# Tiny_UniProg.net
KiCad netlist of a schematic drawn in EAGLE
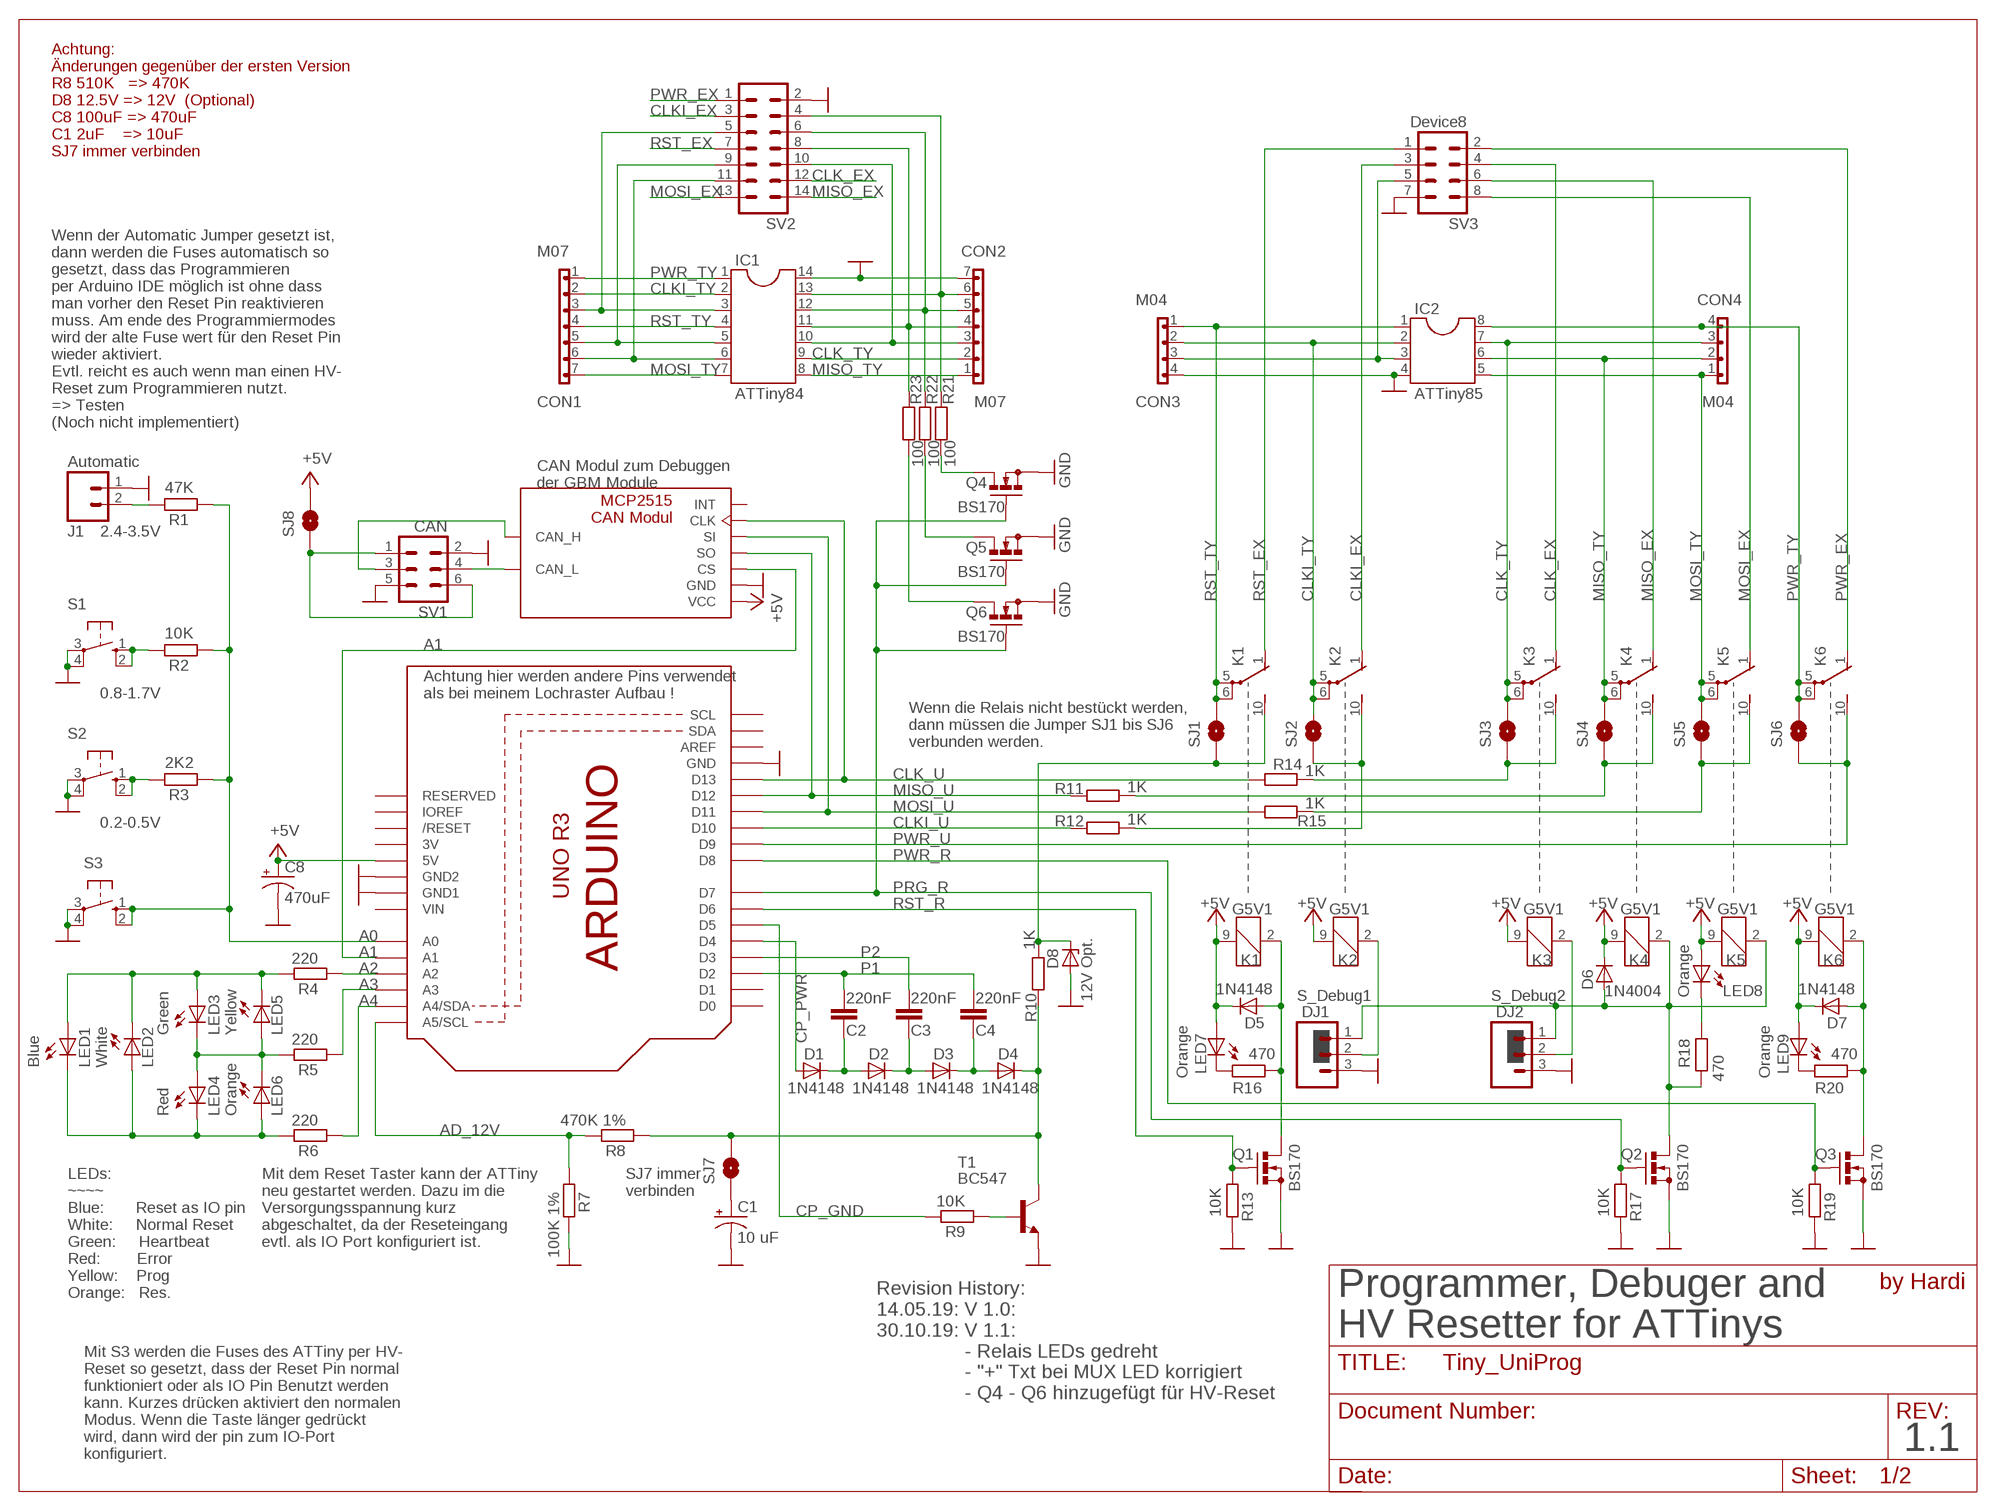
[diagram p0: schematic, sheet 1]
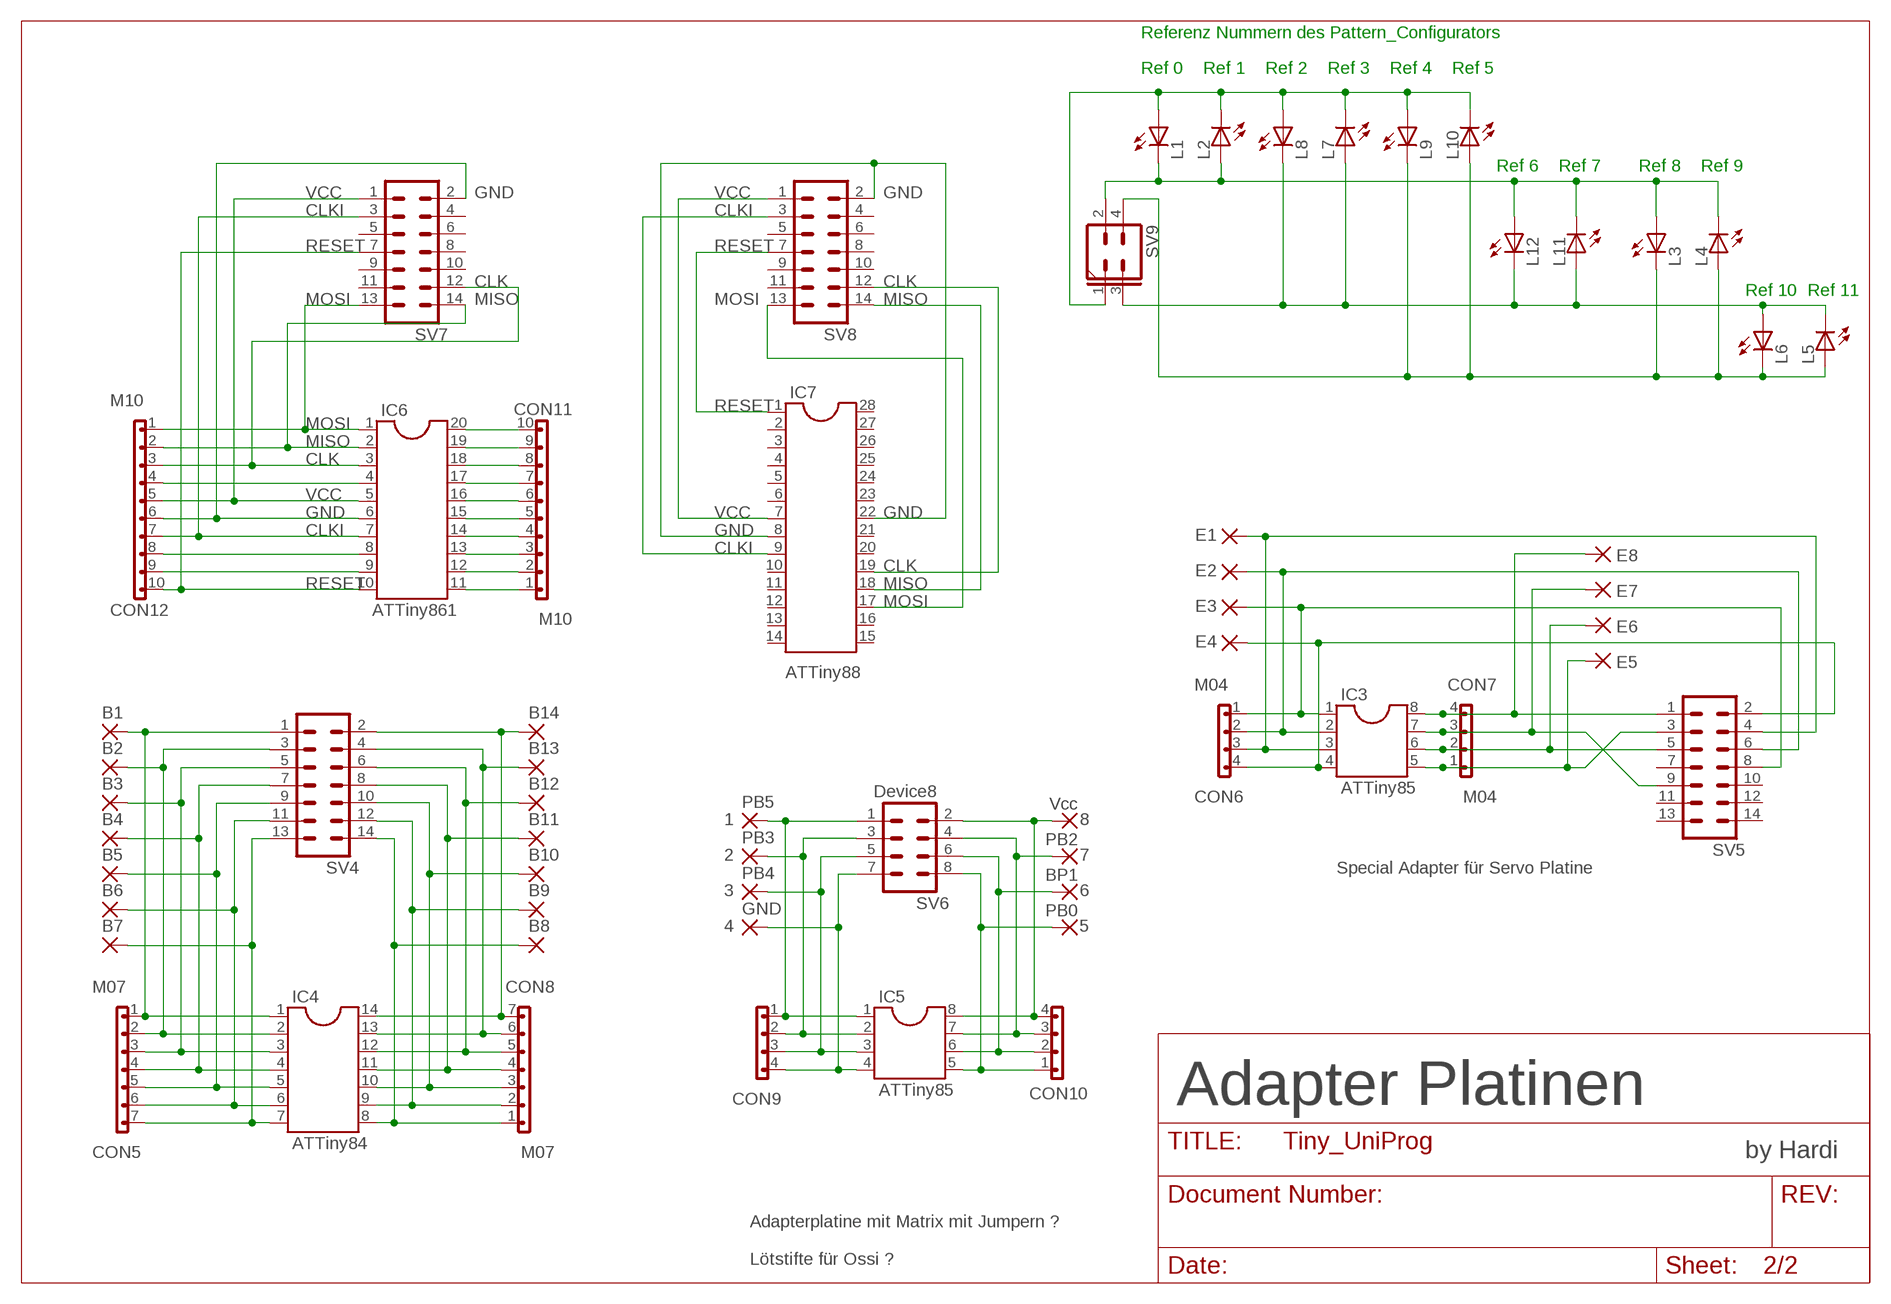
[diagram p1: schematic, sheet 2]

(export (version "E")
  (design (tool "Eeschema 10.0.6"))
  (components
    (comp (ref "1")
      (value "PB5")
      (footprint "eagle-import:2,54_1,0")
      (libsource (lib "eagle-import") (part "2,54/1,0"))
    )
    (comp (ref "2")
      (value "PB3")
      (footprint "eagle-import:2,54_1,0")
      (libsource (lib "eagle-import") (part "2,54/1,0"))
    )
    (comp (ref "3")
      (value "PB4")
      (footprint "eagle-import:2,54_1,0")
      (libsource (lib "eagle-import") (part "2,54/1,0"))
    )
    (comp (ref "4")
      (value "GND")
      (footprint "eagle-import:2,54_1,0")
      (libsource (lib "eagle-import") (part "2,54/1,0"))
    )
    (comp (ref "5")
      (value "PB0")
      (footprint "eagle-import:2,54_1,0")
      (libsource (lib "eagle-import") (part "2,54/1,0"))
    )
    (comp (ref "6")
      (value "BP1")
      (footprint "eagle-import:2,54_1,0")
      (libsource (lib "eagle-import") (part "2,54/1,0"))
    )
    (comp (ref "7")
      (value "PB2")
      (footprint "eagle-import:2,54_1,0")
      (libsource (lib "eagle-import") (part "2,54/1,0"))
    )
    (comp (ref "8")
      (value "Vcc")
      (footprint "eagle-import:2,54_1,0")
      (libsource (lib "eagle-import") (part "2,54/1,0"))
    )
    (comp (ref "B1")
      (value "2,54/1,0")
      (footprint "eagle-import:2,54_1,0")
      (libsource (lib "eagle-import") (part "2,54/1,0"))
    )
    (comp (ref "B2")
      (value "2,54/1,0")
      (footprint "eagle-import:2,54_1,0")
      (libsource (lib "eagle-import") (part "2,54/1,0"))
    )
    (comp (ref "B3")
      (value "2,54/1,0")
      (footprint "eagle-import:2,54_1,0")
      (libsource (lib "eagle-import") (part "2,54/1,0"))
    )
    (comp (ref "B4")
      (value "2,54/1,0")
      (footprint "eagle-import:2,54_1,0")
      (libsource (lib "eagle-import") (part "2,54/1,0"))
    )
    (comp (ref "B5")
      (value "2,54/1,0")
      (footprint "eagle-import:2,54_1,0")
      (libsource (lib "eagle-import") (part "2,54/1,0"))
    )
    (comp (ref "B6")
      (value "2,54/1,0")
      (footprint "eagle-import:2,54_1,0")
      (libsource (lib "eagle-import") (part "2,54/1,0"))
    )
    (comp (ref "B7")
      (value "2,54/1,0")
      (footprint "eagle-import:2,54_1,0")
      (libsource (lib "eagle-import") (part "2,54/1,0"))
    )
    (comp (ref "B8")
      (value "2,54/1,0")
      (footprint "eagle-import:2,54_1,0")
      (libsource (lib "eagle-import") (part "2,54/1,0"))
    )
    (comp (ref "B9")
      (value "2,54/1,0")
      (footprint "eagle-import:2,54_1,0")
      (libsource (lib "eagle-import") (part "2,54/1,0"))
    )
    (comp (ref "B10")
      (value "2,54/1,0")
      (footprint "eagle-import:2,54_1,0")
      (libsource (lib "eagle-import") (part "2,54/1,0"))
    )
    (comp (ref "B11")
      (value "2,54/1,0")
      (footprint "eagle-import:2,54_1,0")
      (libsource (lib "eagle-import") (part "2,54/1,0"))
    )
    (comp (ref "B12")
      (value "2,54/1,0")
      (footprint "eagle-import:2,54_1,0")
      (libsource (lib "eagle-import") (part "2,54/1,0"))
    )
    (comp (ref "B13")
      (value "2,54/1,0")
      (footprint "eagle-import:2,54_1,0")
      (libsource (lib "eagle-import") (part "2,54/1,0"))
    )
    (comp (ref "B14")
      (value "2,54/1,0")
      (footprint "eagle-import:2,54_1,0")
      (libsource (lib "eagle-import") (part "2,54/1,0"))
    )
    (comp (ref "CON5")
      (value "M07")
      (footprint "eagle-import:1X07")
      (libsource (lib "eagle-import") (part "M07"))
    )
    (comp (ref "CON6")
      (value "M04")
      (footprint "eagle-import:1X04")
      (libsource (lib "eagle-import") (part "M04"))
    )
    (comp (ref "CON7")
      (value "M04")
      (footprint "eagle-import:1X04")
      (libsource (lib "eagle-import") (part "M04"))
    )
    (comp (ref "CON8")
      (value "M07")
      (footprint "eagle-import:1X07")
      (libsource (lib "eagle-import") (part "M07"))
    )
    (comp (ref "CON9")
      (value "M04")
      (footprint "eagle-import:1X04")
      (libsource (lib "eagle-import") (part "M04"))
    )
    (comp (ref "CON10")
      (value "M04")
      (footprint "eagle-import:1X04")
      (libsource (lib "eagle-import") (part "M04"))
    )
    (comp (ref "CON11")
      (value "M10")
      (footprint "eagle-import:1X10")
      (libsource (lib "eagle-import") (part "M10"))
    )
    (comp (ref "CON12")
      (value "M10")
      (footprint "eagle-import:1X10")
      (libsource (lib "eagle-import") (part "M10"))
    )
    (comp (ref "E1")
      (value "2,54/1,0")
      (footprint "eagle-import:2,54_1,0")
      (libsource (lib "eagle-import") (part "2,54/1,0"))
    )
    (comp (ref "E2")
      (value "2,54/1,0")
      (footprint "eagle-import:2,54_1,0")
      (libsource (lib "eagle-import") (part "2,54/1,0"))
    )
    (comp (ref "E3")
      (value "2,54/1,0")
      (footprint "eagle-import:2,54_1,0")
      (libsource (lib "eagle-import") (part "2,54/1,0"))
    )
    (comp (ref "E4")
      (value "2,54/1,0")
      (footprint "eagle-import:2,54_1,0")
      (libsource (lib "eagle-import") (part "2,54/1,0"))
    )
    (comp (ref "E5")
      (value "2,54/1,0")
      (footprint "eagle-import:2,54_1,0")
      (libsource (lib "eagle-import") (part "2,54/1,0"))
    )
    (comp (ref "E6")
      (value "2,54/1,0")
      (footprint "eagle-import:2,54_1,0")
      (libsource (lib "eagle-import") (part "2,54/1,0"))
    )
    (comp (ref "E7")
      (value "2,54/1,0")
      (footprint "eagle-import:2,54_1,0")
      (libsource (lib "eagle-import") (part "2,54/1,0"))
    )
    (comp (ref "E8")
      (value "2,54/1,0")
      (footprint "eagle-import:2,54_1,0")
      (libsource (lib "eagle-import") (part "2,54/1,0"))
    )
    (comp (ref "IC3")
      (value "ATTiny85")
      (footprint "eagle-import:DIL08")
      (libsource (lib "eagle-import") (part "DIL8"))
    )
    (comp (ref "IC4")
      (value "ATTiny84")
      (footprint "eagle-import:DIL14")
      (libsource (lib "eagle-import") (part "DIL14"))
    )
    (comp (ref "IC5")
      (value "ATTiny85")
      (footprint "eagle-import:DIL08")
      (libsource (lib "eagle-import") (part "DIL8"))
    )
    (comp (ref "IC6")
      (value "ATTiny861")
      (footprint "eagle-import:DIL20")
      (libsource (lib "eagle-import") (part "DIL20"))
    )
    (comp (ref "IC7")
      (value "DIL28-3")
      (footprint "eagle-import:DIL28-3")
      (libsource (lib "eagle-import") (part "DIL28-3"))
    )
    (comp (ref "L1")
      (value "LED3MM")
      (footprint "eagle-import:LED3MM")
      (libsource (lib "eagle-import") (part "LED3MM"))
    )
    (comp (ref "L2")
      (value "LED3MM")
      (footprint "eagle-import:LED3MM")
      (libsource (lib "eagle-import") (part "LED3MM"))
    )
    (comp (ref "L3")
      (value "LED3MM")
      (footprint "eagle-import:LED3MM")
      (libsource (lib "eagle-import") (part "LED3MM"))
    )
    (comp (ref "L4")
      (value "LED3MM")
      (footprint "eagle-import:LED3MM")
      (libsource (lib "eagle-import") (part "LED3MM"))
    )
    (comp (ref "L5")
      (value "LED3MM")
      (footprint "eagle-import:LED3MM")
      (libsource (lib "eagle-import") (part "LED3MM"))
    )
    (comp (ref "L6")
      (value "LED3MM")
      (footprint "eagle-import:LED3MM")
      (libsource (lib "eagle-import") (part "LED3MM"))
    )
    (comp (ref "L7")
      (value "LED3MM")
      (footprint "eagle-import:LED3MM")
      (libsource (lib "eagle-import") (part "LED3MM"))
    )
    (comp (ref "L8")
      (value "LED3MM")
      (footprint "eagle-import:LED3MM")
      (libsource (lib "eagle-import") (part "LED3MM"))
    )
    (comp (ref "L9")
      (value "LED3MM")
      (footprint "eagle-import:LED3MM")
      (libsource (lib "eagle-import") (part "LED3MM"))
    )
    (comp (ref "L10")
      (value "LED3MM")
      (footprint "eagle-import:LED3MM")
      (libsource (lib "eagle-import") (part "LED3MM"))
    )
    (comp (ref "L11")
      (value "LED3MM")
      (footprint "eagle-import:LED3MM")
      (libsource (lib "eagle-import") (part "LED3MM"))
    )
    (comp (ref "L12")
      (value "LED3MM")
      (footprint "eagle-import:LED3MM")
      (libsource (lib "eagle-import") (part "LED3MM"))
    )
    (comp (ref "SV4")
      (value "ML14")
      (footprint "eagle-import:ML14")
      (libsource (lib "eagle-import") (part "ML14"))
    )
    (comp (ref "SV5")
      (value "ML14")
      (footprint "eagle-import:ML14")
      (libsource (lib "eagle-import") (part "ML14"))
    )
    (comp (ref "SV6")
      (value "Device8")
      (footprint "eagle-import:CON-HARTING-ML_ML08")
      (libsource (lib "eagle-import") (part "CON-HARTING-ML_ML08"))
    )
    (comp (ref "SV7")
      (value "ML14")
      (footprint "eagle-import:ML14")
      (libsource (lib "eagle-import") (part "ML14"))
    )
    (comp (ref "SV8")
      (value "ML14")
      (footprint "eagle-import:ML14")
      (libsource (lib "eagle-import") (part "ML14"))
    )
    (comp (ref "SV9")
      (value "MA02-2MUX-SIGNAL")
      (footprint "eagle-import:MUX-SIGNAL")
      (libsource (lib "eagle-import") (part "MA02-2MUX-SIGNAL"))
    )
    (comp (ref "C1")
      (value "10 uF")
      (footprint "eagle-import:CPOL-RADIAL-10UF-63V")
      (libsource (lib "eagle-import") (part "100UF-25V-20%(PTH)D5MM"))
    )
    (comp (ref "C2")
      (value "220nF")
      (footprint "eagle-import:C050-024X044")
      (libsource (lib "eagle-import") (part "C-EU050-024X044"))
    )
    (comp (ref "C3")
      (value "220nF")
      (footprint "eagle-import:C050-024X044")
      (libsource (lib "eagle-import") (part "C-EU050-024X044"))
    )
    (comp (ref "C4")
      (value "220nF")
      (footprint "eagle-import:C050-024X044")
      (libsource (lib "eagle-import") (part "C-EU050-024X044"))
    )
    (comp (ref "C8")
      (value "470uF")
      (footprint "eagle-import:SPARKFUN-CAPACITORS_CPOL-RADIAL-100UF-25V")
      (libsource (lib "eagle-import") (part "SPARKFUN-CAPACITORS_100UF-25V-20%(PTH)"))
    )
    (comp (ref "CAN1")
      (value "MCP2515_CAN_MODUL")
      (footprint "eagle-import:MCP2515_CAN_MODUL")
      (libsource (lib "eagle-import") (part "MCP2515_CAN_MODUL"))
    )
    (comp (ref "CON1")
      (value "M07")
      (footprint "eagle-import:1X07")
      (libsource (lib "eagle-import") (part "M07"))
    )
    (comp (ref "CON2")
      (value "M07")
      (footprint "eagle-import:1X07")
      (libsource (lib "eagle-import") (part "M07"))
    )
    (comp (ref "CON3")
      (value "M04")
      (footprint "eagle-import:1X04")
      (libsource (lib "eagle-import") (part "M04"))
    )
    (comp (ref "CON4")
      (value "M04")
      (footprint "eagle-import:1X04")
      (libsource (lib "eagle-import") (part "M04"))
    )
    (comp (ref "D1")
      (value "1N4148")
      (footprint "eagle-import:DO35-2")
      (libsource (lib "eagle-import") (part "1N4148DO35-2"))
    )
    (comp (ref "D2")
      (value "1N4148")
      (footprint "eagle-import:DO35-2")
      (libsource (lib "eagle-import") (part "1N4148DO35-2"))
    )
    (comp (ref "D3")
      (value "1N4148")
      (footprint "eagle-import:DO35-2")
      (libsource (lib "eagle-import") (part "1N4148DO35-2"))
    )
    (comp (ref "D4")
      (value "1N4148")
      (footprint "eagle-import:DO35-2")
      (libsource (lib "eagle-import") (part "1N4148DO35-2"))
    )
    (comp (ref "D5")
      (value "1N4148")
      (footprint "eagle-import:DO35-2")
      (libsource (lib "eagle-import") (part "1N4148DO35-2"))
    )
    (comp (ref "D6")
      (value "1N4004")
      (footprint "eagle-import:DO35-2")
      (libsource (lib "eagle-import") (part "1N4004DO35-2"))
    )
    (comp (ref "D7")
      (value "1N4148")
      (footprint "eagle-import:DO35-2")
      (libsource (lib "eagle-import") (part "1N4148DO35-2"))
    )
    (comp (ref "D8")
      (value "12V Opt.")
      (footprint "eagle-import:ZDIO-2.5")
      (libsource (lib "eagle-import") (part "ZENER-DIODEZD-2.5"))
    )
    (comp (ref "DJ1")
      (value "S_Debug1")
      (footprint "eagle-import:1X03")
      (libsource (lib "eagle-import") (part "M03PTH"))
    )
    (comp (ref "DJ2")
      (value "S_Debug2")
      (footprint "eagle-import:1X03")
      (libsource (lib "eagle-import") (part "M03PTH"))
    )
    (comp (ref "IC1")
      (value "ATTiny84")
      (footprint "eagle-import:DIL14")
      (libsource (lib "eagle-import") (part "DIL14"))
    )
    (comp (ref "IC2")
      (value "ATTiny85")
      (footprint "eagle-import:DIL08")
      (libsource (lib "eagle-import") (part "DIL8"))
    )
    (comp (ref "J1")
      (value "Automatic")
      (footprint "eagle-import:1X02")
      (libsource (lib "eagle-import") (part "M02PTH"))
    )
    (comp (ref "K1")
      (value "G5V1")
      (footprint "eagle-import:G5V1")
      (fields (field (name "MPN") "G5V-1-DC24"))
      (libsource (lib "eagle-import") (part "G5V1"))
    )
    (comp (ref "K2")
      (value "G5V1")
      (footprint "eagle-import:G5V1")
      (fields (field (name "MPN") "G5V-1-DC24"))
      (libsource (lib "eagle-import") (part "G5V1"))
    )
    (comp (ref "K3")
      (value "G5V1")
      (footprint "eagle-import:G5V1")
      (fields (field (name "MPN") "G5V-1-DC24"))
      (libsource (lib "eagle-import") (part "G5V1"))
    )
    (comp (ref "K4")
      (value "G5V1")
      (footprint "eagle-import:G5V1")
      (fields (field (name "MPN") "G5V-1-DC24"))
      (libsource (lib "eagle-import") (part "G5V1"))
    )
    (comp (ref "K5")
      (value "G5V1")
      (footprint "eagle-import:G5V1")
      (fields (field (name "MPN") "G5V-1-DC24"))
      (libsource (lib "eagle-import") (part "G5V1"))
    )
    (comp (ref "K6")
      (value "G5V1")
      (footprint "eagle-import:G5V1")
      (fields (field (name "MPN") "G5V-1-DC24"))
      (libsource (lib "eagle-import") (part "G5V1"))
    )
    (comp (ref "LED1")
      (value "Blue")
      (footprint "eagle-import:LED3MM")
      (libsource (lib "eagle-import") (part "LED3MM"))
    )
    (comp (ref "LED2")
      (value "White")
      (footprint "eagle-import:LED3MM")
      (libsource (lib "eagle-import") (part "LED3MM"))
    )
    (comp (ref "LED3")
      (value "Green")
      (footprint "eagle-import:LED3MM")
      (libsource (lib "eagle-import") (part "LED3MM"))
    )
    (comp (ref "LED4")
      (value "Red")
      (footprint "eagle-import:LED3MM")
      (libsource (lib "eagle-import") (part "LED3MM"))
    )
    (comp (ref "LED5")
      (value "Yellow")
      (footprint "eagle-import:LED3MM")
      (libsource (lib "eagle-import") (part "LED3MM"))
    )
    (comp (ref "LED6")
      (value "Orange")
      (footprint "eagle-import:LED3MM")
      (libsource (lib "eagle-import") (part "LED3MM"))
    )
    (comp (ref "LED7")
      (value "Orange")
      (footprint "eagle-import:LED3MM")
      (libsource (lib "eagle-import") (part "LED3MM"))
    )
    (comp (ref "LED8")
      (value "Orange")
      (footprint "eagle-import:LED3MM")
      (libsource (lib "eagle-import") (part "LED3MM"))
    )
    (comp (ref "LED9")
      (value "Orange")
      (footprint "eagle-import:LED3MM")
      (libsource (lib "eagle-import") (part "LED3MM"))
    )
    (comp (ref "Q1")
      (value "BS170")
      (footprint "eagle-import:SOT54E")
      (libsource (lib "eagle-import") (part "BS170"))
    )
    (comp (ref "Q2")
      (value "BS170")
      (footprint "eagle-import:SOT54E")
      (libsource (lib "eagle-import") (part "BS170"))
    )
    (comp (ref "Q3")
      (value "BS170")
      (footprint "eagle-import:SOT54E")
      (libsource (lib "eagle-import") (part "BS170"))
    )
    (comp (ref "Q4")
      (value "BS170")
      (footprint "eagle-import:SOT54E")
      (libsource (lib "eagle-import") (part "BS170"))
    )
    (comp (ref "Q5")
      (value "BS170")
      (footprint "eagle-import:SOT54E")
      (libsource (lib "eagle-import") (part "BS170"))
    )
    (comp (ref "Q6")
      (value "BS170")
      (footprint "eagle-import:SOT54E")
      (libsource (lib "eagle-import") (part "BS170"))
    )
    (comp (ref "R1")
      (value "47K")
      (footprint "eagle-import:0204_7")
      (libsource (lib "eagle-import") (part "R0204/7"))
    )
    (comp (ref "R2")
      (value "10K")
      (footprint "eagle-import:0204_7")
      (libsource (lib "eagle-import") (part "R0204/7"))
    )
    (comp (ref "R3")
      (value "2K2")
      (footprint "eagle-import:0204_2V")
      (libsource (lib "eagle-import") (part "R0204/2V"))
    )
    (comp (ref "R4")
      (value "220")
      (footprint "eagle-import:0204_2V")
      (libsource (lib "eagle-import") (part "R0204/2V"))
    )
    (comp (ref "R5")
      (value "220")
      (footprint "eagle-import:0204_2V")
      (libsource (lib "eagle-import") (part "R0204/2V"))
    )
    (comp (ref "R6")
      (value "220")
      (footprint "eagle-import:0204_2V")
      (libsource (lib "eagle-import") (part "R0204/2V"))
    )
    (comp (ref "R7")
      (value "100K 1%")
      (footprint "eagle-import:0204_2V")
      (libsource (lib "eagle-import") (part "R0204/2V"))
    )
    (comp (ref "R8")
      (value "470K 1%")
      (footprint "eagle-import:0204_7")
      (libsource (lib "eagle-import") (part "R0204/7"))
    )
    (comp (ref "R9")
      (value "10K")
      (footprint "eagle-import:0204_2V")
      (libsource (lib "eagle-import") (part "R0204/2V"))
    )
    (comp (ref "R10")
      (value "1K")
      (footprint "eagle-import:0204_2V")
      (libsource (lib "eagle-import") (part "R0204/2V"))
    )
    (comp (ref "R11")
      (value "1K")
      (footprint "eagle-import:0204_2V")
      (libsource (lib "eagle-import") (part "R0204/2V"))
    )
    (comp (ref "R12")
      (value "1K")
      (footprint "eagle-import:0204_2V")
      (libsource (lib "eagle-import") (part "R0204/2V"))
    )
    (comp (ref "R13")
      (value "10K")
      (footprint "eagle-import:0204_2V")
      (libsource (lib "eagle-import") (part "R0204/2V"))
    )
    (comp (ref "R14")
      (value "1K")
      (footprint "eagle-import:0204_2V")
      (libsource (lib "eagle-import") (part "R0204/2V"))
    )
    (comp (ref "R15")
      (value "1K")
      (footprint "eagle-import:0204_2V")
      (libsource (lib "eagle-import") (part "R0204/2V"))
    )
    (comp (ref "R16")
      (value "470")
      (footprint "eagle-import:0204_2V")
      (libsource (lib "eagle-import") (part "R0204/2V"))
    )
    (comp (ref "R17")
      (value "10K")
      (footprint "eagle-import:0204_2V")
      (libsource (lib "eagle-import") (part "R0204/2V"))
    )
    (comp (ref "R18")
      (value "470")
      (footprint "eagle-import:0204_2V")
      (libsource (lib "eagle-import") (part "R0204/2V"))
    )
    (comp (ref "R19")
      (value "10K")
      (footprint "eagle-import:0204_2V")
      (libsource (lib "eagle-import") (part "R0204/2V"))
    )
    (comp (ref "R20")
      (value "470")
      (footprint "eagle-import:0204_2V")
      (libsource (lib "eagle-import") (part "R0204/2V"))
    )
    (comp (ref "R21")
      (value "100")
      (footprint "eagle-import:0204_2V")
      (libsource (lib "eagle-import") (part "R0204/2V"))
    )
    (comp (ref "R22")
      (value "100")
      (footprint "eagle-import:0204_2V")
      (libsource (lib "eagle-import") (part "R0204/2V"))
    )
    (comp (ref "R23")
      (value "100")
      (footprint "eagle-import:0204_2V")
      (libsource (lib "eagle-import") (part "R0204/2V"))
    )
    (comp (ref "S1")
      (value "10-XX")
      (footprint "eagle-import:B3F-10XX")
      (fields (field (name "MPN") "B3F-1000"))
      (libsource (lib "eagle-import") (part "10-XX"))
    )
    (comp (ref "S2")
      (value "10-XX")
      (footprint "eagle-import:B3F-10XX")
      (fields (field (name "MPN") "B3F-1000"))
      (libsource (lib "eagle-import") (part "10-XX"))
    )
    (comp (ref "S3")
      (value "10-XX")
      (footprint "eagle-import:B3F-10XX")
      (fields (field (name "MPN") "B3F-1000"))
      (libsource (lib "eagle-import") (part "10-XX"))
    )
    (comp (ref "SJ1")
      (value "SOLDERJUMPERNO")
      (footprint "eagle-import:SJ_2S-NO")
      (libsource (lib "eagle-import") (part "SOLDERJUMPERNO"))
    )
    (comp (ref "SJ2")
      (value "SOLDERJUMPERNO")
      (footprint "eagle-import:SJ_2S-NO")
      (libsource (lib "eagle-import") (part "SOLDERJUMPERNO"))
    )
    (comp (ref "SJ3")
      (value "SOLDERJUMPERNO")
      (footprint "eagle-import:SJ_2S-NO")
      (libsource (lib "eagle-import") (part "SOLDERJUMPERNO"))
    )
    (comp (ref "SJ4")
      (value "SOLDERJUMPERNO")
      (footprint "eagle-import:SJ_2S-NO")
      (libsource (lib "eagle-import") (part "SOLDERJUMPERNO"))
    )
    (comp (ref "SJ5")
      (value "SOLDERJUMPERNO")
      (footprint "eagle-import:SJ_2S-NO")
      (libsource (lib "eagle-import") (part "SOLDERJUMPERNO"))
    )
    (comp (ref "SJ6")
      (value "SOLDERJUMPERNO")
      (footprint "eagle-import:SJ_2S-NO")
      (libsource (lib "eagle-import") (part "SOLDERJUMPERNO"))
    )
    (comp (ref "SJ7")
      (value "SOLDERJUMPERNO")
      (footprint "eagle-import:SJ_2S-NO")
      (libsource (lib "eagle-import") (part "SOLDERJUMPERNO"))
    )
    (comp (ref "SJ8")
      (value "SOLDERJUMPERNO")
      (footprint "eagle-import:SJ_2S-NO")
      (libsource (lib "eagle-import") (part "SOLDERJUMPERNO"))
    )
    (comp (ref "SV1")
      (value "CAN")
      (footprint "eagle-import:ML6")
      (libsource (lib "eagle-import") (part "ML6"))
    )
    (comp (ref "SV2")
      (value "ML14")
      (footprint "eagle-import:ML14")
      (libsource (lib "eagle-import") (part "ML14"))
    )
    (comp (ref "SV3")
      (value "Device8")
      (footprint "eagle-import:CON-HARTING-ML_ML08")
      (libsource (lib "eagle-import") (part "CON-HARTING-ML_ML08"))
    )
    (comp (ref "T1")
      (value "BC547")
      (footprint "eagle-import:TO92")
      (libsource (lib "eagle-import") (part "BC547"))
    )
    (comp (ref "U1")
      (value "ARDUINOR3-DIMENSION")
      (footprint "eagle-import:ARDUINOR3")
      (libsource (lib "eagle-import") (part "ARDUINOR3-DIMENSION"))
    )
  )
  (nets
    (net (code "1") (name "+5V") (class "Default")
      (node (ref "C8") (pin "1") (pinfunction "+_1") (pintype "passive"))
      (node (ref "CAN1") (pin "1") (pinfunction "VCC_1") (pintype "power_in"))
      (node (ref "D5") (pin "C") (pinfunction "C_C") (pintype "passive"))
      (node (ref "D6") (pin "C") (pinfunction "C_C") (pintype "passive"))
      (node (ref "D7") (pin "C") (pinfunction "C_C") (pintype "passive"))
      (node (ref "K1") (pin "9") (pinfunction "2_9") (pintype "passive"))
      (node (ref "K2") (pin "9") (pinfunction "2_9") (pintype "passive"))
      (node (ref "K3") (pin "9") (pinfunction "2_9") (pintype "passive"))
      (node (ref "K4") (pin "9") (pinfunction "2_9") (pintype "passive"))
      (node (ref "K5") (pin "9") (pinfunction "2_9") (pintype "passive"))
      (node (ref "K6") (pin "9") (pinfunction "2_9") (pintype "passive"))
      (node (ref "LED7") (pin "A") (pinfunction "A_A") (pintype "passive"))
      (node (ref "LED8") (pin "A") (pinfunction "A_A") (pintype "passive"))
      (node (ref "LED9") (pin "A") (pinfunction "A_A") (pintype "passive"))
      (node (ref "SJ8") (pin "2") (pinfunction "2_2") (pintype "passive"))
      (node (ref "U1") (pin "5V") (pinfunction "5V_5V") (pintype "power_in"))
    )
    (net (code "2") (name "3V") (class "Default")
      (node (ref "U1") (pin "3V") (pinfunction "3V_3V") (pintype "power_in"))
    )
    (net (code "3") (name "A0") (class "Default")
      (node (ref "R1") (pin "1") (pinfunction "1_1") (pintype "passive"))
      (node (ref "R2") (pin "1") (pinfunction "1_1") (pintype "passive"))
      (node (ref "R3") (pin "1") (pinfunction "1_1") (pintype "passive"))
      (node (ref "S3") (pin "1") (pinfunction "S_1") (pintype "passive"))
      (node (ref "S3") (pin "2") (pinfunction "S1_2") (pintype "passive"))
      (node (ref "U1") (pin "A0") (pinfunction "A0_A0") (pintype "bidirectional"))
    )
    (net (code "4") (name "A1") (class "Default")
      (node (ref "CAN1") (pin "3") (pinfunction "CS_3") (pintype "input"))
      (node (ref "U1") (pin "A1") (pinfunction "A1_A1") (pintype "bidirectional"))
    )
    (net (code "5") (name "A2") (class "Default")
      (node (ref "R4") (pin "1") (pinfunction "1_1") (pintype "passive"))
      (node (ref "U1") (pin "A2") (pinfunction "A2_A2") (pintype "bidirectional"))
    )
    (net (code "6") (name "A3") (class "Default")
      (node (ref "R5") (pin "1") (pinfunction "1_1") (pintype "passive"))
      (node (ref "U1") (pin "A3") (pinfunction "A3_A3") (pintype "bidirectional"))
    )
    (net (code "7") (name "A4") (class "Default")
      (node (ref "R6") (pin "1") (pinfunction "1_1") (pintype "passive"))
      (node (ref "U1") (pin "A4") (pinfunction "A4/SDA_A4") (pintype "bidirectional"))
    )
    (net (code "8") (name "AD_12V") (class "Default")
      (node (ref "R7") (pin "1") (pinfunction "1_1") (pintype "passive"))
      (node (ref "R8") (pin "2") (pinfunction "2_2") (pintype "passive"))
      (node (ref "U1") (pin "A5") (pinfunction "A5/SCL_A5") (pintype "bidirectional"))
    )
    (net (code "9") (name "CLKI_EX") (class "Default")
      (node (ref "K2") (pin "1") (pinfunction "O_1") (pintype "passive"))
      (node (ref "SV2") (pin "3") (pinfunction "3_3") (pintype "passive"))
      (node (ref "SV3") (pin "3") (pinfunction "3_3") (pintype "passive"))
    )
    (net (code "10") (name "CLKI_TY") (class "Default")
      (node (ref "CON1") (pin "2") (pinfunction "2_2") (pintype "passive"))
      (node (ref "CON3") (pin "2") (pinfunction "2_2") (pintype "passive"))
      (node (ref "IC1") (pin "2") (pinfunction "2_2") (pintype "passive"))
      (node (ref "IC2") (pin "2") (pinfunction "2_2") (pintype "passive"))
      (node (ref "K2") (pin "5") (pinfunction "P_5") (pintype "passive"))
      (node (ref "K2") (pin "6") (pinfunction "P_6") (pintype "passive"))
      (node (ref "SJ2") (pin "2") (pinfunction "2_2") (pintype "passive"))
    )
    (net (code "11") (name "CLKI_U") (class "Default")
      (node (ref "R12") (pin "1") (pinfunction "1_1") (pintype "passive"))
      (node (ref "U1") (pin "D10") (pinfunction "D10_D10") (pintype "bidirectional"))
    )
    (net (code "12") (name "CLK_EX") (class "Default")
      (node (ref "K3") (pin "1") (pinfunction "O_1") (pintype "passive"))
      (node (ref "SV2") (pin "12") (pinfunction "12_12") (pintype "passive"))
      (node (ref "SV3") (pin "4") (pinfunction "4_4") (pintype "passive"))
    )
    (net (code "13") (name "CLK_TY") (class "Default")
      (node (ref "CON2") (pin "2") (pinfunction "2_2") (pintype "passive"))
      (node (ref "CON4") (pin "3") (pinfunction "3_3") (pintype "passive"))
      (node (ref "IC1") (pin "9") (pinfunction "9_9") (pintype "passive"))
      (node (ref "IC2") (pin "7") (pinfunction "7_7") (pintype "passive"))
      (node (ref "K3") (pin "5") (pinfunction "P_5") (pintype "passive"))
      (node (ref "K3") (pin "6") (pinfunction "P_6") (pintype "passive"))
      (node (ref "SJ3") (pin "2") (pinfunction "2_2") (pintype "passive"))
    )
    (net (code "14") (name "CLK_U") (class "Default")
      (node (ref "CAN1") (pin "6") (pinfunction "CLK_6") (pintype "input"))
      (node (ref "R14") (pin "1") (pinfunction "1_1") (pintype "passive"))
      (node (ref "U1") (pin "D13") (pinfunction "D13_D13") (pintype "bidirectional"))
    )
    (net (code "15") (name "CP_GND") (class "Default")
      (node (ref "R9") (pin "2") (pinfunction "2_2") (pintype "passive"))
      (node (ref "U1") (pin "D5") (pinfunction "D5_D5") (pintype "bidirectional"))
    )
    (net (code "16") (name "CP_PWR") (class "Default")
      (node (ref "D1") (pin "A") (pinfunction "A_A") (pintype "passive"))
      (node (ref "U1") (pin "D4") (pinfunction "D4_D4") (pintype "bidirectional"))
    )
    (net (code "17") (name "GND") (class "Default")
      (node (ref "C1") (pin "2") (pinfunction "-_2") (pintype "passive"))
      (node (ref "C8") (pin "2") (pinfunction "-_2") (pintype "passive"))
      (node (ref "CAN1") (pin "2") (pinfunction "GND_2") (pintype "power_in"))
      (node (ref "CON2") (pin "7") (pinfunction "7_7") (pintype "passive"))
      (node (ref "CON3") (pin "4") (pinfunction "4_4") (pintype "passive"))
      (node (ref "D8") (pin "A") (pinfunction "A_A") (pintype "passive"))
      (node (ref "DJ1") (pin "3") (pinfunction "3_3") (pintype "passive"))
      (node (ref "DJ2") (pin "3") (pinfunction "3_3") (pintype "passive"))
      (node (ref "IC1") (pin "14") (pinfunction "14_14") (pintype "passive"))
      (node (ref "IC2") (pin "4") (pinfunction "4_4") (pintype "passive"))
      (node (ref "J1") (pin "1") (pinfunction "1_1") (pintype "passive"))
      (node (ref "Q1") (pin "S") (pinfunction "S_S") (pintype "passive"))
      (node (ref "Q2") (pin "S") (pinfunction "S_S") (pintype "passive"))
      (node (ref "Q3") (pin "S") (pinfunction "S_S") (pintype "passive"))
      (node (ref "Q4") (pin "S") (pinfunction "S_S") (pintype "passive"))
      (node (ref "Q5") (pin "S") (pinfunction "S_S") (pintype "passive"))
      (node (ref "Q6") (pin "S") (pinfunction "S_S") (pintype "passive"))
      (node (ref "R13") (pin "2") (pinfunction "2_2") (pintype "passive"))
      (node (ref "R17") (pin "2") (pinfunction "2_2") (pintype "passive"))
      (node (ref "R19") (pin "2") (pinfunction "2_2") (pintype "passive"))
      (node (ref "R7") (pin "2") (pinfunction "2_2") (pintype "passive"))
      (node (ref "S1") (pin "3") (pinfunction "P_3") (pintype "passive"))
      (node (ref "S1") (pin "4") (pinfunction "P1_4") (pintype "passive"))
      (node (ref "S2") (pin "3") (pinfunction "P_3") (pintype "passive"))
      (node (ref "S2") (pin "4") (pinfunction "P1_4") (pintype "passive"))
      (node (ref "S3") (pin "3") (pinfunction "P_3") (pintype "passive"))
      (node (ref "S3") (pin "4") (pinfunction "P1_4") (pintype "passive"))
      (node (ref "SV1") (pin "2") (pinfunction "2_2") (pintype "passive"))
      (node (ref "SV1") (pin "5") (pinfunction "5_5") (pintype "passive"))
      (node (ref "SV2") (pin "2") (pinfunction "2_2") (pintype "passive"))
      (node (ref "SV3") (pin "7") (pinfunction "7_7") (pintype "passive"))
      (node (ref "T1") (pin "1") (pinfunction "E_1") (pintype "passive"))
      (node (ref "U1") (pin "GND") (pinfunction "GND_GND") (pintype "power_in"))
      (node (ref "U1") (pin "GND1") (pinfunction "GND1_GND1") (pintype "power_in"))
      (node (ref "U1") (pin "GND2") (pinfunction "GND2_GND2") (pintype "power_in"))
    )
    (net (code "18") (name "MISO_EX") (class "Default")
      (node (ref "K4") (pin "1") (pinfunction "O_1") (pintype "passive"))
      (node (ref "SV2") (pin "14") (pinfunction "14_14") (pintype "passive"))
      (node (ref "SV3") (pin "6") (pinfunction "6_6") (pintype "passive"))
    )
    (net (code "19") (name "MISO_TY") (class "Default")
      (node (ref "CON2") (pin "1") (pinfunction "1_1") (pintype "passive"))
      (node (ref "CON4") (pin "2") (pinfunction "2_2") (pintype "passive"))
      (node (ref "IC1") (pin "8") (pinfunction "8_8") (pintype "passive"))
      (node (ref "IC2") (pin "6") (pinfunction "6_6") (pintype "passive"))
      (node (ref "K4") (pin "5") (pinfunction "P_5") (pintype "passive"))
      (node (ref "K4") (pin "6") (pinfunction "P_6") (pintype "passive"))
      (node (ref "SJ4") (pin "2") (pinfunction "2_2") (pintype "passive"))
    )
    (net (code "20") (name "MISO_U") (class "Default")
      (node (ref "CAN1") (pin "4") (pinfunction "SO_4") (pintype "output"))
      (node (ref "R11") (pin "1") (pinfunction "1_1") (pintype "passive"))
      (node (ref "U1") (pin "D12") (pinfunction "D12_D12") (pintype "bidirectional"))
    )
    (net (code "21") (name "MOSI_EX") (class "Default")
      (node (ref "K5") (pin "1") (pinfunction "O_1") (pintype "passive"))
      (node (ref "SV2") (pin "13") (pinfunction "13_13") (pintype "passive"))
      (node (ref "SV3") (pin "8") (pinfunction "8_8") (pintype "passive"))
    )
    (net (code "22") (name "MOSI_TY") (class "Default")
      (node (ref "CON1") (pin "7") (pinfunction "7_7") (pintype "passive"))
      (node (ref "CON4") (pin "1") (pinfunction "1_1") (pintype "passive"))
      (node (ref "IC1") (pin "7") (pinfunction "7_7") (pintype "passive"))
      (node (ref "IC2") (pin "5") (pinfunction "5_5") (pintype "passive"))
      (node (ref "K5") (pin "5") (pinfunction "P_5") (pintype "passive"))
      (node (ref "K5") (pin "6") (pinfunction "P_6") (pintype "passive"))
      (node (ref "SJ5") (pin "2") (pinfunction "2_2") (pintype "passive"))
    )
    (net (code "23") (name "MOSI_U") (class "Default")
      (node (ref "CAN1") (pin "5") (pinfunction "SI_5") (pintype "input"))
      (node (ref "R15") (pin "1") (pinfunction "1_1") (pintype "passive"))
      (node (ref "U1") (pin "D11") (pinfunction "D11_D11") (pintype "bidirectional"))
    )
    (net (code "24") (name "Net-(1-P)") (class "Default")
      (node (ref "1") (pin "1") (pinfunction "P_1") (pintype "passive"))
      (node (ref "CON9") (pin "1") (pinfunction "1_1") (pintype "passive"))
      (node (ref "IC5") (pin "1") (pinfunction "1_1") (pintype "passive"))
      (node (ref "SV6") (pin "1") (pinfunction "1_1") (pintype "passive"))
    )
    (net (code "25") (name "Net-(2-P)") (class "Default")
      (node (ref "2") (pin "1") (pinfunction "P_1") (pintype "passive"))
      (node (ref "CON9") (pin "2") (pinfunction "2_2") (pintype "passive"))
      (node (ref "IC5") (pin "2") (pinfunction "2_2") (pintype "passive"))
      (node (ref "SV6") (pin "3") (pinfunction "3_3") (pintype "passive"))
    )
    (net (code "26") (name "Net-(3-P)") (class "Default")
      (node (ref "3") (pin "1") (pinfunction "P_1") (pintype "passive"))
      (node (ref "CON9") (pin "3") (pinfunction "3_3") (pintype "passive"))
      (node (ref "IC5") (pin "3") (pinfunction "3_3") (pintype "passive"))
      (node (ref "SV6") (pin "5") (pinfunction "5_5") (pintype "passive"))
    )
    (net (code "27") (name "Net-(4-P)") (class "Default")
      (node (ref "4") (pin "1") (pinfunction "P_1") (pintype "passive"))
      (node (ref "CON9") (pin "4") (pinfunction "4_4") (pintype "passive"))
      (node (ref "IC5") (pin "4") (pinfunction "4_4") (pintype "passive"))
      (node (ref "SV6") (pin "7") (pinfunction "7_7") (pintype "passive"))
    )
    (net (code "28") (name "Net-(5-P)") (class "Default")
      (node (ref "5") (pin "1") (pinfunction "P_1") (pintype "passive"))
      (node (ref "CON10") (pin "1") (pinfunction "1_1") (pintype "passive"))
      (node (ref "IC5") (pin "5") (pinfunction "5_5") (pintype "passive"))
      (node (ref "SV6") (pin "8") (pinfunction "8_8") (pintype "passive"))
    )
    (net (code "29") (name "Net-(6-P)") (class "Default")
      (node (ref "6") (pin "1") (pinfunction "P_1") (pintype "passive"))
      (node (ref "CON10") (pin "2") (pinfunction "2_2") (pintype "passive"))
      (node (ref "IC5") (pin "6") (pinfunction "6_6") (pintype "passive"))
      (node (ref "SV6") (pin "6") (pinfunction "6_6") (pintype "passive"))
    )
    (net (code "30") (name "Net-(7-P)") (class "Default")
      (node (ref "7") (pin "1") (pinfunction "P_1") (pintype "passive"))
      (node (ref "CON10") (pin "3") (pinfunction "3_3") (pintype "passive"))
      (node (ref "IC5") (pin "7") (pinfunction "7_7") (pintype "passive"))
      (node (ref "SV6") (pin "4") (pinfunction "4_4") (pintype "passive"))
    )
    (net (code "31") (name "Net-(8-P)") (class "Default")
      (node (ref "8") (pin "1") (pinfunction "P_1") (pintype "passive"))
      (node (ref "CON10") (pin "4") (pinfunction "4_4") (pintype "passive"))
      (node (ref "IC5") (pin "8") (pinfunction "8_8") (pintype "passive"))
      (node (ref "SV6") (pin "2") (pinfunction "2_2") (pintype "passive"))
    )
    (net (code "32") (name "Net-(B1-P)") (class "Default")
      (node (ref "B1") (pin "1") (pinfunction "P_1") (pintype "passive"))
      (node (ref "CON5") (pin "1") (pinfunction "1_1") (pintype "passive"))
      (node (ref "IC4") (pin "1") (pinfunction "1_1") (pintype "passive"))
      (node (ref "SV4") (pin "1") (pinfunction "1_1") (pintype "passive"))
    )
    (net (code "33") (name "Net-(B2-P)") (class "Default")
      (node (ref "B2") (pin "1") (pinfunction "P_1") (pintype "passive"))
      (node (ref "CON5") (pin "2") (pinfunction "2_2") (pintype "passive"))
      (node (ref "IC4") (pin "2") (pinfunction "2_2") (pintype "passive"))
      (node (ref "SV4") (pin "3") (pinfunction "3_3") (pintype "passive"))
    )
    (net (code "34") (name "Net-(B3-P)") (class "Default")
      (node (ref "B3") (pin "1") (pinfunction "P_1") (pintype "passive"))
      (node (ref "CON5") (pin "3") (pinfunction "3_3") (pintype "passive"))
      (node (ref "IC4") (pin "3") (pinfunction "3_3") (pintype "passive"))
      (node (ref "SV4") (pin "5") (pinfunction "5_5") (pintype "passive"))
    )
    (net (code "35") (name "Net-(B4-P)") (class "Default")
      (node (ref "B4") (pin "1") (pinfunction "P_1") (pintype "passive"))
      (node (ref "CON5") (pin "4") (pinfunction "4_4") (pintype "passive"))
      (node (ref "IC4") (pin "4") (pinfunction "4_4") (pintype "passive"))
      (node (ref "SV4") (pin "7") (pinfunction "7_7") (pintype "passive"))
    )
    (net (code "36") (name "Net-(B5-P)") (class "Default")
      (node (ref "B5") (pin "1") (pinfunction "P_1") (pintype "passive"))
      (node (ref "CON5") (pin "5") (pinfunction "5_5") (pintype "passive"))
      (node (ref "IC4") (pin "5") (pinfunction "5_5") (pintype "passive"))
      (node (ref "SV4") (pin "9") (pinfunction "9_9") (pintype "passive"))
    )
    (net (code "37") (name "Net-(B6-P)") (class "Default")
      (node (ref "B6") (pin "1") (pinfunction "P_1") (pintype "passive"))
      (node (ref "CON5") (pin "6") (pinfunction "6_6") (pintype "passive"))
      (node (ref "IC4") (pin "6") (pinfunction "6_6") (pintype "passive"))
      (node (ref "SV4") (pin "11") (pinfunction "11_11") (pintype "passive"))
    )
    (net (code "38") (name "Net-(B7-P)") (class "Default")
      (node (ref "B7") (pin "1") (pinfunction "P_1") (pintype "passive"))
      (node (ref "CON5") (pin "7") (pinfunction "7_7") (pintype "passive"))
      (node (ref "IC4") (pin "7") (pinfunction "7_7") (pintype "passive"))
      (node (ref "SV4") (pin "13") (pinfunction "13_13") (pintype "passive"))
    )
    (net (code "39") (name "Net-(B8-P)") (class "Default")
      (node (ref "B8") (pin "1") (pinfunction "P_1") (pintype "passive"))
      (node (ref "CON8") (pin "1") (pinfunction "1_1") (pintype "passive"))
      (node (ref "IC4") (pin "8") (pinfunction "8_8") (pintype "passive"))
      (node (ref "SV4") (pin "14") (pinfunction "14_14") (pintype "passive"))
    )
    (net (code "40") (name "Net-(B9-P)") (class "Default")
      (node (ref "B9") (pin "1") (pinfunction "P_1") (pintype "passive"))
      (node (ref "CON8") (pin "2") (pinfunction "2_2") (pintype "passive"))
      (node (ref "IC4") (pin "9") (pinfunction "9_9") (pintype "passive"))
      (node (ref "SV4") (pin "12") (pinfunction "12_12") (pintype "passive"))
    )
    (net (code "41") (name "Net-(B10-P)") (class "Default")
      (node (ref "B10") (pin "1") (pinfunction "P_1") (pintype "passive"))
      (node (ref "CON8") (pin "3") (pinfunction "3_3") (pintype "passive"))
      (node (ref "IC4") (pin "10") (pinfunction "10_10") (pintype "passive"))
      (node (ref "SV4") (pin "10") (pinfunction "10_10") (pintype "passive"))
    )
    (net (code "42") (name "Net-(B11-P)") (class "Default")
      (node (ref "B11") (pin "1") (pinfunction "P_1") (pintype "passive"))
      (node (ref "CON8") (pin "4") (pinfunction "4_4") (pintype "passive"))
      (node (ref "IC4") (pin "11") (pinfunction "11_11") (pintype "passive"))
      (node (ref "SV4") (pin "8") (pinfunction "8_8") (pintype "passive"))
    )
    (net (code "43") (name "Net-(B12-P)") (class "Default")
      (node (ref "B12") (pin "1") (pinfunction "P_1") (pintype "passive"))
      (node (ref "CON8") (pin "5") (pinfunction "5_5") (pintype "passive"))
      (node (ref "IC4") (pin "12") (pinfunction "12_12") (pintype "passive"))
      (node (ref "SV4") (pin "6") (pinfunction "6_6") (pintype "passive"))
    )
    (net (code "44") (name "Net-(B13-P)") (class "Default")
      (node (ref "B13") (pin "1") (pinfunction "P_1") (pintype "passive"))
      (node (ref "CON8") (pin "6") (pinfunction "6_6") (pintype "passive"))
      (node (ref "IC4") (pin "13") (pinfunction "13_13") (pintype "passive"))
      (node (ref "SV4") (pin "4") (pinfunction "4_4") (pintype "passive"))
    )
    (net (code "45") (name "Net-(B14-P)") (class "Default")
      (node (ref "B14") (pin "1") (pinfunction "P_1") (pintype "passive"))
      (node (ref "CON8") (pin "7") (pinfunction "7_7") (pintype "passive"))
      (node (ref "IC4") (pin "14") (pinfunction "14_14") (pintype "passive"))
      (node (ref "SV4") (pin "2") (pinfunction "2_2") (pintype "passive"))
    )
    (net (code "46") (name "Net-(C1-+)") (class "Default")
      (node (ref "C1") (pin "1") (pinfunction "+_1") (pintype "passive"))
      (node (ref "SJ7") (pin "1") (pinfunction "1_1") (pintype "passive"))
    )
    (net (code "47") (name "Net-(C2-Pad2)") (class "Default")
      (node (ref "C2") (pin "2") (pinfunction "2_2") (pintype "passive"))
      (node (ref "D1") (pin "C") (pinfunction "C_C") (pintype "passive"))
      (node (ref "D2") (pin "A") (pinfunction "A_A") (pintype "passive"))
    )
    (net (code "48") (name "Net-(C3-Pad2)") (class "Default")
      (node (ref "C3") (pin "2") (pinfunction "2_2") (pintype "passive"))
      (node (ref "D2") (pin "C") (pinfunction "C_C") (pintype "passive"))
      (node (ref "D3") (pin "A") (pinfunction "A_A") (pintype "passive"))
    )
    (net (code "49") (name "Net-(C4-Pad2)") (class "Default")
      (node (ref "C4") (pin "2") (pinfunction "2_2") (pintype "passive"))
      (node (ref "D3") (pin "C") (pinfunction "C_C") (pintype "passive"))
      (node (ref "D4") (pin "A") (pinfunction "A_A") (pintype "passive"))
    )
    (net (code "50") (name "Net-(CAN1-CAN_H)") (class "Default")
      (node (ref "CAN1") (pin "9") (pinfunction "CAN_H_9") (pintype "bidirectional"))
      (node (ref "SV1") (pin "3") (pinfunction "3_3") (pintype "passive"))
    )
    (net (code "51") (name "Net-(CAN1-CAN_L)") (class "Default")
      (node (ref "CAN1") (pin "8") (pinfunction "CAN_L_8") (pintype "bidirectional"))
      (node (ref "SV1") (pin "4") (pinfunction "4_4") (pintype "passive"))
    )
    (net (code "52") (name "Net-(CON1-Pad3)") (class "Default")
      (node (ref "CON1") (pin "3") (pinfunction "3_3") (pintype "passive"))
      (node (ref "IC1") (pin "3") (pinfunction "3_3") (pintype "passive"))
      (node (ref "SV2") (pin "5") (pinfunction "5_5") (pintype "passive"))
    )
    (net (code "53") (name "Net-(CON1-Pad5)") (class "Default")
      (node (ref "CON1") (pin "5") (pinfunction "5_5") (pintype "passive"))
      (node (ref "IC1") (pin "5") (pinfunction "5_5") (pintype "passive"))
      (node (ref "SV2") (pin "9") (pinfunction "9_9") (pintype "passive"))
    )
    (net (code "54") (name "Net-(CON1-Pad6)") (class "Default")
      (node (ref "CON1") (pin "6") (pinfunction "6_6") (pintype "passive"))
      (node (ref "IC1") (pin "6") (pinfunction "6_6") (pintype "passive"))
      (node (ref "SV2") (pin "11") (pinfunction "11_11") (pintype "passive"))
    )
    (net (code "55") (name "Net-(CON2-Pad3)") (class "Default")
      (node (ref "CON2") (pin "3") (pinfunction "3_3") (pintype "passive"))
      (node (ref "IC1") (pin "10") (pinfunction "10_10") (pintype "passive"))
      (node (ref "SV2") (pin "10") (pinfunction "10_10") (pintype "passive"))
    )
    (net (code "56") (name "Net-(CON2-Pad4)") (class "Default")
      (node (ref "CON2") (pin "4") (pinfunction "4_4") (pintype "passive"))
      (node (ref "IC1") (pin "11") (pinfunction "11_11") (pintype "passive"))
      (node (ref "R23") (pin "2") (pinfunction "2_2") (pintype "passive"))
      (node (ref "SV2") (pin "8") (pinfunction "8_8") (pintype "passive"))
    )
    (net (code "57") (name "Net-(CON2-Pad5)") (class "Default")
      (node (ref "CON2") (pin "5") (pinfunction "5_5") (pintype "passive"))
      (node (ref "IC1") (pin "12") (pinfunction "12_12") (pintype "passive"))
      (node (ref "R22") (pin "2") (pinfunction "2_2") (pintype "passive"))
      (node (ref "SV2") (pin "6") (pinfunction "6_6") (pintype "passive"))
    )
    (net (code "58") (name "Net-(CON2-Pad6)") (class "Default")
      (node (ref "CON2") (pin "6") (pinfunction "6_6") (pintype "passive"))
      (node (ref "IC1") (pin "13") (pinfunction "13_13") (pintype "passive"))
      (node (ref "R21") (pin "2") (pinfunction "2_2") (pintype "passive"))
      (node (ref "SV2") (pin "4") (pinfunction "4_4") (pintype "passive"))
    )
    (net (code "59") (name "Net-(CON3-Pad3)") (class "Default")
      (node (ref "CON3") (pin "3") (pinfunction "3_3") (pintype "passive"))
      (node (ref "IC2") (pin "3") (pinfunction "3_3") (pintype "passive"))
      (node (ref "SV3") (pin "5") (pinfunction "5_5") (pintype "passive"))
    )
    (net (code "60") (name "Net-(CON11-Pad1)") (class "Default")
      (node (ref "CON11") (pin "1") (pinfunction "1_1") (pintype "passive"))
      (node (ref "IC6") (pin "11") (pinfunction "11_11") (pintype "passive"))
    )
    (net (code "61") (name "Net-(CON11-Pad2)") (class "Default")
      (node (ref "CON11") (pin "2") (pinfunction "2_2") (pintype "passive"))
      (node (ref "IC6") (pin "12") (pinfunction "12_12") (pintype "passive"))
    )
    (net (code "62") (name "Net-(CON11-Pad3)") (class "Default")
      (node (ref "CON11") (pin "3") (pinfunction "3_3") (pintype "passive"))
      (node (ref "IC6") (pin "13") (pinfunction "13_13") (pintype "passive"))
    )
    (net (code "63") (name "Net-(CON11-Pad4)") (class "Default")
      (node (ref "CON11") (pin "4") (pinfunction "4_4") (pintype "passive"))
      (node (ref "IC6") (pin "14") (pinfunction "14_14") (pintype "passive"))
    )
    (net (code "64") (name "Net-(CON11-Pad5)") (class "Default")
      (node (ref "CON11") (pin "5") (pinfunction "5_5") (pintype "passive"))
      (node (ref "IC6") (pin "15") (pinfunction "15_15") (pintype "passive"))
    )
    (net (code "65") (name "Net-(CON11-Pad6)") (class "Default")
      (node (ref "CON11") (pin "6") (pinfunction "6_6") (pintype "passive"))
      (node (ref "IC6") (pin "16") (pinfunction "16_16") (pintype "passive"))
    )
    (net (code "66") (name "Net-(CON11-Pad7)") (class "Default")
      (node (ref "CON11") (pin "7") (pinfunction "7_7") (pintype "passive"))
      (node (ref "IC6") (pin "17") (pinfunction "17_17") (pintype "passive"))
    )
    (net (code "67") (name "Net-(CON11-Pad8)") (class "Default")
      (node (ref "CON11") (pin "8") (pinfunction "8_8") (pintype "passive"))
      (node (ref "IC6") (pin "18") (pinfunction "18_18") (pintype "passive"))
    )
    (net (code "68") (name "Net-(CON11-Pad9)") (class "Default")
      (node (ref "CON11") (pin "9") (pinfunction "9_9") (pintype "passive"))
      (node (ref "IC6") (pin "19") (pinfunction "19_19") (pintype "passive"))
    )
    (net (code "69") (name "Net-(CON11-Pad10)") (class "Default")
      (node (ref "CON11") (pin "10") (pinfunction "10_10") (pintype "passive"))
      (node (ref "IC6") (pin "20") (pinfunction "20_20") (pintype "passive"))
    )
    (net (code "70") (name "Net-(CON12-Pad1)") (class "Default")
      (node (ref "CON12") (pin "1") (pinfunction "1_1") (pintype "passive"))
      (node (ref "IC6") (pin "1") (pinfunction "1_1") (pintype "passive"))
      (node (ref "SV7") (pin "13") (pinfunction "13_13") (pintype "passive"))
    )
    (net (code "71") (name "Net-(CON12-Pad2)") (class "Default")
      (node (ref "CON12") (pin "2") (pinfunction "2_2") (pintype "passive"))
      (node (ref "IC6") (pin "2") (pinfunction "2_2") (pintype "passive"))
      (node (ref "SV7") (pin "14") (pinfunction "14_14") (pintype "passive"))
    )
    (net (code "72") (name "Net-(CON12-Pad3)") (class "Default")
      (node (ref "CON12") (pin "3") (pinfunction "3_3") (pintype "passive"))
      (node (ref "IC6") (pin "3") (pinfunction "3_3") (pintype "passive"))
      (node (ref "SV7") (pin "12") (pinfunction "12_12") (pintype "passive"))
    )
    (net (code "73") (name "Net-(CON12-Pad4)") (class "Default")
      (node (ref "CON12") (pin "4") (pinfunction "4_4") (pintype "passive"))
      (node (ref "IC6") (pin "4") (pinfunction "4_4") (pintype "passive"))
    )
    (net (code "74") (name "Net-(CON12-Pad5)") (class "Default")
      (node (ref "CON12") (pin "5") (pinfunction "5_5") (pintype "passive"))
      (node (ref "IC6") (pin "5") (pinfunction "5_5") (pintype "passive"))
      (node (ref "SV7") (pin "1") (pinfunction "1_1") (pintype "passive"))
    )
    (net (code "75") (name "Net-(CON12-Pad6)") (class "Default")
      (node (ref "CON12") (pin "6") (pinfunction "6_6") (pintype "passive"))
      (node (ref "IC6") (pin "6") (pinfunction "6_6") (pintype "passive"))
      (node (ref "SV7") (pin "2") (pinfunction "2_2") (pintype "passive"))
    )
    (net (code "76") (name "Net-(CON12-Pad7)") (class "Default")
      (node (ref "CON12") (pin "7") (pinfunction "7_7") (pintype "passive"))
      (node (ref "IC6") (pin "7") (pinfunction "7_7") (pintype "passive"))
      (node (ref "SV7") (pin "3") (pinfunction "3_3") (pintype "passive"))
    )
    (net (code "77") (name "Net-(CON12-Pad8)") (class "Default")
      (node (ref "CON12") (pin "8") (pinfunction "8_8") (pintype "passive"))
      (node (ref "IC6") (pin "8") (pinfunction "8_8") (pintype "passive"))
    )
    (net (code "78") (name "Net-(CON12-Pad9)") (class "Default")
      (node (ref "CON12") (pin "9") (pinfunction "9_9") (pintype "passive"))
      (node (ref "IC6") (pin "9") (pinfunction "9_9") (pintype "passive"))
    )
    (net (code "79") (name "Net-(CON12-Pad10)") (class "Default")
      (node (ref "CON12") (pin "10") (pinfunction "10_10") (pintype "passive"))
      (node (ref "IC6") (pin "10") (pinfunction "10_10") (pintype "passive"))
      (node (ref "SV7") (pin "7") (pinfunction "7_7") (pintype "passive"))
    )
    (net (code "80") (name "Net-(E1-P)") (class "Default")
      (node (ref "CON6") (pin "3") (pinfunction "3_3") (pintype "passive"))
      (node (ref "E1") (pin "1") (pinfunction "P_1") (pintype "passive"))
      (node (ref "IC3") (pin "3") (pinfunction "3_3") (pintype "passive"))
      (node (ref "SV5") (pin "4") (pinfunction "4_4") (pintype "passive"))
    )
    (net (code "81") (name "Net-(E2-P)") (class "Default")
      (node (ref "CON6") (pin "2") (pinfunction "2_2") (pintype "passive"))
      (node (ref "E2") (pin "1") (pinfunction "P_1") (pintype "passive"))
      (node (ref "IC3") (pin "2") (pinfunction "2_2") (pintype "passive"))
      (node (ref "SV5") (pin "6") (pinfunction "6_6") (pintype "passive"))
    )
    (net (code "82") (name "Net-(E3-P)") (class "Default")
      (node (ref "CON6") (pin "1") (pinfunction "1_1") (pintype "passive"))
      (node (ref "E3") (pin "1") (pinfunction "P_1") (pintype "passive"))
      (node (ref "IC3") (pin "1") (pinfunction "1_1") (pintype "passive"))
      (node (ref "SV5") (pin "8") (pinfunction "8_8") (pintype "passive"))
    )
    (net (code "83") (name "Net-(E4-P)") (class "Default")
      (node (ref "CON6") (pin "4") (pinfunction "4_4") (pintype "passive"))
      (node (ref "E4") (pin "1") (pinfunction "P_1") (pintype "passive"))
      (node (ref "IC3") (pin "4") (pinfunction "4_4") (pintype "passive"))
      (node (ref "SV5") (pin "2") (pinfunction "2_2") (pintype "passive"))
    )
    (net (code "84") (name "Net-(E5-P)") (class "Default")
      (node (ref "CON7") (pin "1") (pinfunction "1_1") (pintype "passive"))
      (node (ref "E5") (pin "1") (pinfunction "P_1") (pintype "passive"))
      (node (ref "IC3") (pin "5") (pinfunction "5_5") (pintype "passive"))
      (node (ref "SV5") (pin "3") (pinfunction "3_3") (pintype "passive"))
    )
    (net (code "85") (name "Net-(E6-P)") (class "Default")
      (node (ref "CON7") (pin "2") (pinfunction "2_2") (pintype "passive"))
      (node (ref "E6") (pin "1") (pinfunction "P_1") (pintype "passive"))
      (node (ref "IC3") (pin "6") (pinfunction "6_6") (pintype "passive"))
      (node (ref "SV5") (pin "5") (pinfunction "5_5") (pintype "passive"))
    )
    (net (code "86") (name "Net-(E7-P)") (class "Default")
      (node (ref "CON7") (pin "3") (pinfunction "3_3") (pintype "passive"))
      (node (ref "E7") (pin "1") (pinfunction "P_1") (pintype "passive"))
      (node (ref "IC3") (pin "7") (pinfunction "7_7") (pintype "passive"))
      (node (ref "SV5") (pin "9") (pinfunction "9_9") (pintype "passive"))
    )
    (net (code "87") (name "Net-(E8-P)") (class "Default")
      (node (ref "CON7") (pin "4") (pinfunction "4_4") (pintype "passive"))
      (node (ref "E8") (pin "1") (pinfunction "P_1") (pintype "passive"))
      (node (ref "IC3") (pin "8") (pinfunction "8_8") (pintype "passive"))
      (node (ref "SV5") (pin "1") (pinfunction "1_1") (pintype "passive"))
    )
    (net (code "88") (name "Net-(IC7-Pad1)") (class "Default")
      (node (ref "IC7") (pin "1") (pinfunction "1_1") (pintype "passive"))
      (node (ref "SV8") (pin "7") (pinfunction "7_7") (pintype "passive"))
    )
    (net (code "89") (name "Net-(IC7-Pad7)") (class "Default")
      (node (ref "IC7") (pin "7") (pinfunction "7_7") (pintype "passive"))
      (node (ref "SV8") (pin "1") (pinfunction "1_1") (pintype "passive"))
    )
    (net (code "90") (name "Net-(IC7-Pad9)") (class "Default")
      (node (ref "IC7") (pin "9") (pinfunction "9_9") (pintype "passive"))
      (node (ref "SV8") (pin "3") (pinfunction "3_3") (pintype "passive"))
    )
    (net (code "91") (name "Net-(IC7-Pad17)") (class "Default")
      (node (ref "IC7") (pin "17") (pinfunction "17_17") (pintype "passive"))
      (node (ref "SV8") (pin "13") (pinfunction "13_13") (pintype "passive"))
    )
    (net (code "92") (name "Net-(IC7-Pad18)") (class "Default")
      (node (ref "IC7") (pin "18") (pinfunction "18_18") (pintype "passive"))
      (node (ref "SV8") (pin "14") (pinfunction "14_14") (pintype "passive"))
    )
    (net (code "93") (name "Net-(IC7-Pad19)") (class "Default")
      (node (ref "IC7") (pin "19") (pinfunction "19_19") (pintype "passive"))
      (node (ref "SV8") (pin "12") (pinfunction "12_12") (pintype "passive"))
    )
    (net (code "94") (name "Net-(IC7-Pad22)") (class "Default")
      (node (ref "IC7") (pin "22") (pinfunction "22_22") (pintype "passive"))
      (node (ref "IC7") (pin "8") (pinfunction "8_8") (pintype "passive"))
      (node (ref "SV8") (pin "2") (pinfunction "2_2") (pintype "passive"))
    )
    (net (code "95") (name "Net-(J1-Pad2)") (class "Default")
      (node (ref "J1") (pin "2") (pinfunction "2_2") (pintype "passive"))
      (node (ref "R1") (pin "2") (pinfunction "2_2") (pintype "passive"))
    )
    (net (code "96") (name "Net-(K1A-1)") (class "Default")
      (node (ref "D5") (pin "A") (pinfunction "A_A") (pintype "passive"))
      (node (ref "K1") (pin "2") (pinfunction "1_2") (pintype "passive"))
      (node (ref "Q1") (pin "D") (pinfunction "D_D") (pintype "passive"))
      (node (ref "R16") (pin "2") (pinfunction "2_2") (pintype "passive"))
    )
    (net (code "97") (name "Net-(K1B-S)") (class "Default")
      (node (ref "D8") (pin "C") (pinfunction "C_C") (pintype "passive"))
      (node (ref "K1") (pin "10") (pinfunction "S_10") (pintype "passive"))
      (node (ref "R10") (pin "1") (pinfunction "1_1") (pintype "passive"))
      (node (ref "SJ1") (pin "1") (pinfunction "1_1") (pintype "passive"))
    )
    (net (code "98") (name "Net-(K2A-1)") (class "Default")
      (node (ref "DJ1") (pin "2") (pinfunction "2_2") (pintype "passive"))
      (node (ref "K2") (pin "2") (pinfunction "1_2") (pintype "passive"))
    )
    (net (code "99") (name "Net-(K2B-S)") (class "Default")
      (node (ref "K2") (pin "10") (pinfunction "S_10") (pintype "passive"))
      (node (ref "R12") (pin "2") (pinfunction "2_2") (pintype "passive"))
      (node (ref "SJ2") (pin "1") (pinfunction "1_1") (pintype "passive"))
    )
    (net (code "100") (name "Net-(K3A-1)") (class "Default")
      (node (ref "DJ2") (pin "2") (pinfunction "2_2") (pintype "passive"))
      (node (ref "K3") (pin "2") (pinfunction "1_2") (pintype "passive"))
    )
    (net (code "101") (name "Net-(K3B-S)") (class "Default")
      (node (ref "K3") (pin "10") (pinfunction "S_10") (pintype "passive"))
      (node (ref "R14") (pin "2") (pinfunction "2_2") (pintype "passive"))
      (node (ref "SJ3") (pin "1") (pinfunction "1_1") (pintype "passive"))
    )
    (net (code "102") (name "Net-(K4A-1)") (class "Default")
      (node (ref "D6") (pin "A") (pinfunction "A_A") (pintype "passive"))
      (node (ref "DJ1") (pin "1") (pinfunction "1_1") (pintype "passive"))
      (node (ref "DJ2") (pin "1") (pinfunction "1_1") (pintype "passive"))
      (node (ref "K4") (pin "2") (pinfunction "1_2") (pintype "passive"))
      (node (ref "K5") (pin "2") (pinfunction "1_2") (pintype "passive"))
      (node (ref "Q2") (pin "D") (pinfunction "D_D") (pintype "passive"))
      (node (ref "R18") (pin "2") (pinfunction "2_2") (pintype "passive"))
    )
    (net (code "103") (name "Net-(K4B-S)") (class "Default")
      (node (ref "K4") (pin "10") (pinfunction "S_10") (pintype "passive"))
      (node (ref "R11") (pin "2") (pinfunction "2_2") (pintype "passive"))
      (node (ref "SJ4") (pin "1") (pinfunction "1_1") (pintype "passive"))
    )
    (net (code "104") (name "Net-(K5B-S)") (class "Default")
      (node (ref "K5") (pin "10") (pinfunction "S_10") (pintype "passive"))
      (node (ref "R15") (pin "2") (pinfunction "2_2") (pintype "passive"))
      (node (ref "SJ5") (pin "1") (pinfunction "1_1") (pintype "passive"))
    )
    (net (code "105") (name "Net-(K6A-1)") (class "Default")
      (node (ref "D7") (pin "A") (pinfunction "A_A") (pintype "passive"))
      (node (ref "K6") (pin "2") (pinfunction "1_2") (pintype "passive"))
      (node (ref "Q3") (pin "D") (pinfunction "D_D") (pintype "passive"))
      (node (ref "R20") (pin "2") (pinfunction "2_2") (pintype "passive"))
    )
    (net (code "106") (name "Net-(L1-C)") (class "Default")
      (node (ref "L1") (pin "K") (pinfunction "C_K") (pintype "passive"))
      (node (ref "L11") (pin "K") (pinfunction "C_K") (pintype "passive"))
      (node (ref "L12") (pin "A") (pinfunction "A_A") (pintype "passive"))
      (node (ref "L2") (pin "A") (pinfunction "A_A") (pintype "passive"))
      (node (ref "L3") (pin "A") (pinfunction "A_A") (pintype "passive"))
      (node (ref "L4") (pin "K") (pinfunction "C_K") (pintype "passive"))
      (node (ref "SV9") (pin "2") (pinfunction "2_2") (pintype "passive"))
    )
    (net (code "107") (name "Net-(L3-C)") (class "Default")
      (node (ref "L10") (pin "A") (pinfunction "A_A") (pintype "passive"))
      (node (ref "L3") (pin "K") (pinfunction "C_K") (pintype "passive"))
      (node (ref "L4") (pin "A") (pinfunction "A_A") (pintype "passive"))
      (node (ref "L5") (pin "A") (pinfunction "A_A") (pintype "passive"))
      (node (ref "L6") (pin "K") (pinfunction "C_K") (pintype "passive"))
      (node (ref "L9") (pin "K") (pinfunction "C_K") (pintype "passive"))
      (node (ref "SV9") (pin "4") (pinfunction "4_4") (pintype "passive"))
    )
    (net (code "108") (name "Net-(L10-C)") (class "Default")
      (node (ref "L1") (pin "A") (pinfunction "A_A") (pintype "passive"))
      (node (ref "L10") (pin "K") (pinfunction "C_K") (pintype "passive"))
      (node (ref "L2") (pin "K") (pinfunction "C_K") (pintype "passive"))
      (node (ref "L7") (pin "K") (pinfunction "C_K") (pintype "passive"))
      (node (ref "L8") (pin "A") (pinfunction "A_A") (pintype "passive"))
      (node (ref "L9") (pin "A") (pinfunction "A_A") (pintype "passive"))
      (node (ref "SV9") (pin "1") (pinfunction "1_1") (pintype "passive"))
    )
    (net (code "109") (name "Net-(L12-C)") (class "Default")
      (node (ref "L11") (pin "A") (pinfunction "A_A") (pintype "passive"))
      (node (ref "L12") (pin "K") (pinfunction "C_K") (pintype "passive"))
      (node (ref "L5") (pin "K") (pinfunction "C_K") (pintype "passive"))
      (node (ref "L6") (pin "A") (pinfunction "A_A") (pintype "passive"))
      (node (ref "L7") (pin "A") (pinfunction "A_A") (pintype "passive"))
      (node (ref "L8") (pin "K") (pinfunction "C_K") (pintype "passive"))
      (node (ref "SV9") (pin "3") (pinfunction "3_3") (pintype "passive"))
    )
    (net (code "110") (name "Net-(LED1-C)") (class "Default")
      (node (ref "LED1") (pin "K") (pinfunction "C_K") (pintype "passive"))
      (node (ref "LED2") (pin "A") (pinfunction "A_A") (pintype "passive"))
      (node (ref "LED4") (pin "K") (pinfunction "C_K") (pintype "passive"))
      (node (ref "LED6") (pin "A") (pinfunction "A_A") (pintype "passive"))
      (node (ref "R6") (pin "2") (pinfunction "2_2") (pintype "passive"))
    )
    (net (code "111") (name "Net-(LED2-C)") (class "Default")
      (node (ref "LED1") (pin "A") (pinfunction "A_A") (pintype "passive"))
      (node (ref "LED2") (pin "K") (pinfunction "C_K") (pintype "passive"))
      (node (ref "LED3") (pin "A") (pinfunction "A_A") (pintype "passive"))
      (node (ref "LED5") (pin "K") (pinfunction "C_K") (pintype "passive"))
      (node (ref "R4") (pin "2") (pinfunction "2_2") (pintype "passive"))
    )
    (net (code "112") (name "Net-(LED3-C)") (class "Default")
      (node (ref "LED3") (pin "K") (pinfunction "C_K") (pintype "passive"))
      (node (ref "LED4") (pin "A") (pinfunction "A_A") (pintype "passive"))
      (node (ref "LED5") (pin "A") (pinfunction "A_A") (pintype "passive"))
      (node (ref "LED6") (pin "K") (pinfunction "C_K") (pintype "passive"))
      (node (ref "R5") (pin "2") (pinfunction "2_2") (pintype "passive"))
    )
    (net (code "113") (name "Net-(LED7-C)") (class "Default")
      (node (ref "LED7") (pin "K") (pinfunction "C_K") (pintype "passive"))
      (node (ref "R16") (pin "1") (pinfunction "1_1") (pintype "passive"))
    )
    (net (code "114") (name "Net-(LED8-C)") (class "Default")
      (node (ref "LED8") (pin "K") (pinfunction "C_K") (pintype "passive"))
      (node (ref "R18") (pin "1") (pinfunction "1_1") (pintype "passive"))
    )
    (net (code "115") (name "Net-(LED9-C)") (class "Default")
      (node (ref "LED9") (pin "K") (pinfunction "C_K") (pintype "passive"))
      (node (ref "R20") (pin "1") (pinfunction "1_1") (pintype "passive"))
    )
    (net (code "116") (name "Net-(Q4-PadD)") (class "Default")
      (node (ref "Q4") (pin "D") (pinfunction "D_D") (pintype "passive"))
      (node (ref "R21") (pin "1") (pinfunction "1_1") (pintype "passive"))
    )
    (net (code "117") (name "Net-(Q5-PadD)") (class "Default")
      (node (ref "Q5") (pin "D") (pinfunction "D_D") (pintype "passive"))
      (node (ref "R22") (pin "1") (pinfunction "1_1") (pintype "passive"))
    )
    (net (code "118") (name "Net-(Q6-PadD)") (class "Default")
      (node (ref "Q6") (pin "D") (pinfunction "D_D") (pintype "passive"))
      (node (ref "R23") (pin "1") (pinfunction "1_1") (pintype "passive"))
    )
    (net (code "119") (name "Net-(S1-S)") (class "Default")
      (node (ref "R2") (pin "2") (pinfunction "2_2") (pintype "passive"))
      (node (ref "S1") (pin "1") (pinfunction "S_1") (pintype "passive"))
      (node (ref "S1") (pin "2") (pinfunction "S1_2") (pintype "passive"))
    )
    (net (code "120") (name "Net-(S2-S)") (class "Default")
      (node (ref "R3") (pin "2") (pinfunction "2_2") (pintype "passive"))
      (node (ref "S2") (pin "1") (pinfunction "S_1") (pintype "passive"))
      (node (ref "S2") (pin "2") (pinfunction "S1_2") (pintype "passive"))
    )
    (net (code "121") (name "Net-(SJ8-Pad1)") (class "Default")
      (node (ref "SJ8") (pin "1") (pinfunction "1_1") (pintype "passive"))
      (node (ref "SV1") (pin "1") (pinfunction "1_1") (pintype "passive"))
      (node (ref "SV1") (pin "6") (pinfunction "6_6") (pintype "passive"))
    )
    (net (code "122") (name "Net-(T1-B)") (class "Default")
      (node (ref "R9") (pin "1") (pinfunction "1_1") (pintype "passive"))
      (node (ref "T1") (pin "2") (pinfunction "B_2") (pintype "passive"))
    )
    (net (code "123") (name "Net-(T1-C)") (class "Default")
      (node (ref "D4") (pin "C") (pinfunction "C_C") (pintype "passive"))
      (node (ref "R10") (pin "2") (pinfunction "2_2") (pintype "passive"))
      (node (ref "R8") (pin "1") (pinfunction "1_1") (pintype "passive"))
      (node (ref "SJ7") (pin "2") (pinfunction "2_2") (pintype "passive"))
      (node (ref "T1") (pin "3") (pinfunction "C_3") (pintype "passive"))
    )
    (net (code "124") (name "P1") (class "Default")
      (node (ref "C2") (pin "1") (pinfunction "1_1") (pintype "passive"))
      (node (ref "C4") (pin "1") (pinfunction "1_1") (pintype "passive"))
      (node (ref "U1") (pin "D2") (pinfunction "D2_D2") (pintype "bidirectional"))
    )
    (net (code "125") (name "P2") (class "Default")
      (node (ref "C3") (pin "1") (pinfunction "1_1") (pintype "passive"))
      (node (ref "U1") (pin "D3") (pinfunction "D3_D3") (pintype "bidirectional"))
    )
    (net (code "126") (name "PRG_R") (class "Default")
      (node (ref "Q2") (pin "G") (pinfunction "G_G") (pintype "passive"))
      (node (ref "Q4") (pin "G") (pinfunction "G_G") (pintype "passive"))
      (node (ref "Q5") (pin "G") (pinfunction "G_G") (pintype "passive"))
      (node (ref "Q6") (pin "G") (pinfunction "G_G") (pintype "passive"))
      (node (ref "R17") (pin "1") (pinfunction "1_1") (pintype "passive"))
      (node (ref "U1") (pin "D7") (pinfunction "D7_D7") (pintype "bidirectional"))
    )
    (net (code "127") (name "PWR_EX") (class "Default")
      (node (ref "K6") (pin "1") (pinfunction "O_1") (pintype "passive"))
      (node (ref "SV2") (pin "1") (pinfunction "1_1") (pintype "passive"))
      (node (ref "SV3") (pin "2") (pinfunction "2_2") (pintype "passive"))
    )
    (net (code "128") (name "PWR_R") (class "Default")
      (node (ref "Q3") (pin "G") (pinfunction "G_G") (pintype "passive"))
      (node (ref "R19") (pin "1") (pinfunction "1_1") (pintype "passive"))
      (node (ref "U1") (pin "D8") (pinfunction "D8_D8") (pintype "bidirectional"))
    )
    (net (code "129") (name "PWR_TY") (class "Default")
      (node (ref "CON1") (pin "1") (pinfunction "1_1") (pintype "passive"))
      (node (ref "CON4") (pin "4") (pinfunction "4_4") (pintype "passive"))
      (node (ref "IC1") (pin "1") (pinfunction "1_1") (pintype "passive"))
      (node (ref "IC2") (pin "8") (pinfunction "8_8") (pintype "passive"))
      (node (ref "K6") (pin "5") (pinfunction "P_5") (pintype "passive"))
      (node (ref "K6") (pin "6") (pinfunction "P_6") (pintype "passive"))
      (node (ref "SJ6") (pin "2") (pinfunction "2_2") (pintype "passive"))
    )
    (net (code "130") (name "PWR_U") (class "Default")
      (node (ref "K6") (pin "10") (pinfunction "S_10") (pintype "passive"))
      (node (ref "SJ6") (pin "1") (pinfunction "1_1") (pintype "passive"))
      (node (ref "U1") (pin "D9") (pinfunction "D9_D9") (pintype "bidirectional"))
    )
    (net (code "131") (name "RST_EX") (class "Default")
      (node (ref "K1") (pin "1") (pinfunction "O_1") (pintype "passive"))
      (node (ref "SV2") (pin "7") (pinfunction "7_7") (pintype "passive"))
      (node (ref "SV3") (pin "1") (pinfunction "1_1") (pintype "passive"))
    )
    (net (code "132") (name "RST_R") (class "Default")
      (node (ref "Q1") (pin "G") (pinfunction "G_G") (pintype "passive"))
      (node (ref "R13") (pin "1") (pinfunction "1_1") (pintype "passive"))
      (node (ref "U1") (pin "D6") (pinfunction "D6_D6") (pintype "bidirectional"))
    )
    (net (code "133") (name "RST_TY") (class "Default")
      (node (ref "CON1") (pin "4") (pinfunction "4_4") (pintype "passive"))
      (node (ref "CON3") (pin "1") (pinfunction "1_1") (pintype "passive"))
      (node (ref "IC1") (pin "4") (pinfunction "4_4") (pintype "passive"))
      (node (ref "IC2") (pin "1") (pinfunction "1_1") (pintype "passive"))
      (node (ref "K1") (pin "5") (pinfunction "P_5") (pintype "passive"))
      (node (ref "K1") (pin "6") (pinfunction "P_6") (pintype "passive"))
      (node (ref "SJ1") (pin "2") (pinfunction "2_2") (pintype "passive"))
    )
    (net (code "134") (name "VIN") (class "Default")
      (node (ref "U1") (pin "VIN") (pinfunction "VIN_VIN") (pintype "power_in"))
    )
    (net (code "135") (name "unconnected-(CAN1-INT-Pad7)") (class "Default")
      (node (ref "CAN1") (pin "7") (pinfunction "INT_7") (pintype "open_collector"))
    )
    (net (code "136") (name "unconnected-(IC7-Pad2)") (class "Default")
      (node (ref "IC7") (pin "2") (pinfunction "2_2") (pintype "passive"))
    )
    (net (code "137") (name "unconnected-(IC7-Pad3)") (class "Default")
      (node (ref "IC7") (pin "3") (pinfunction "3_3") (pintype "passive"))
    )
    (net (code "138") (name "unconnected-(IC7-Pad4)") (class "Default")
      (node (ref "IC7") (pin "4") (pinfunction "4_4") (pintype "passive"))
    )
    (net (code "139") (name "unconnected-(IC7-Pad5)") (class "Default")
      (node (ref "IC7") (pin "5") (pinfunction "5_5") (pintype "passive"))
    )
    (net (code "140") (name "unconnected-(IC7-Pad6)") (class "Default")
      (node (ref "IC7") (pin "6") (pinfunction "6_6") (pintype "passive"))
    )
    (net (code "141") (name "unconnected-(IC7-Pad10)") (class "Default")
      (node (ref "IC7") (pin "10") (pinfunction "10_10") (pintype "passive"))
    )
    (net (code "142") (name "unconnected-(IC7-Pad11)") (class "Default")
      (node (ref "IC7") (pin "11") (pinfunction "11_11") (pintype "passive"))
    )
    (net (code "143") (name "unconnected-(IC7-Pad12)") (class "Default")
      (node (ref "IC7") (pin "12") (pinfunction "12_12") (pintype "passive"))
    )
    (net (code "144") (name "unconnected-(IC7-Pad13)") (class "Default")
      (node (ref "IC7") (pin "13") (pinfunction "13_13") (pintype "passive"))
    )
    (net (code "145") (name "unconnected-(IC7-Pad14)") (class "Default")
      (node (ref "IC7") (pin "14") (pinfunction "14_14") (pintype "passive"))
    )
    (net (code "146") (name "unconnected-(IC7-Pad15)") (class "Default")
      (node (ref "IC7") (pin "15") (pinfunction "15_15") (pintype "passive"))
    )
    (net (code "147") (name "unconnected-(IC7-Pad16)") (class "Default")
      (node (ref "IC7") (pin "16") (pinfunction "16_16") (pintype "passive"))
    )
    (net (code "148") (name "unconnected-(IC7-Pad20)") (class "Default")
      (node (ref "IC7") (pin "20") (pinfunction "20_20") (pintype "passive"))
    )
    (net (code "149") (name "unconnected-(IC7-Pad21)") (class "Default")
      (node (ref "IC7") (pin "21") (pinfunction "21_21") (pintype "passive"))
    )
    (net (code "150") (name "unconnected-(IC7-Pad23)") (class "Default")
      (node (ref "IC7") (pin "23") (pinfunction "23_23") (pintype "passive"))
    )
    (net (code "151") (name "unconnected-(IC7-Pad24)") (class "Default")
      (node (ref "IC7") (pin "24") (pinfunction "24_24") (pintype "passive"))
    )
    (net (code "152") (name "unconnected-(IC7-Pad25)") (class "Default")
      (node (ref "IC7") (pin "25") (pinfunction "25_25") (pintype "passive"))
    )
    (net (code "153") (name "unconnected-(IC7-Pad26)") (class "Default")
      (node (ref "IC7") (pin "26") (pinfunction "26_26") (pintype "passive"))
    )
    (net (code "154") (name "unconnected-(IC7-Pad27)") (class "Default")
      (node (ref "IC7") (pin "27") (pinfunction "27_27") (pintype "passive"))
    )
    (net (code "155") (name "unconnected-(IC7-Pad28)") (class "Default")
      (node (ref "IC7") (pin "28") (pinfunction "28_28") (pintype "passive"))
    )
    (net (code "156") (name "unconnected-(SV5-Pad7)") (class "Default")
      (node (ref "SV5") (pin "7") (pinfunction "7_7") (pintype "passive"))
    )
    (net (code "157") (name "unconnected-(SV5-Pad10)") (class "Default")
      (node (ref "SV5") (pin "10") (pinfunction "10_10") (pintype "passive"))
    )
    (net (code "158") (name "unconnected-(SV5-Pad11)") (class "Default")
      (node (ref "SV5") (pin "11") (pinfunction "11_11") (pintype "passive"))
    )
    (net (code "159") (name "unconnected-(SV5-Pad12)") (class "Default")
      (node (ref "SV5") (pin "12") (pinfunction "12_12") (pintype "passive"))
    )
    (net (code "160") (name "unconnected-(SV5-Pad13)") (class "Default")
      (node (ref "SV5") (pin "13") (pinfunction "13_13") (pintype "passive"))
    )
    (net (code "161") (name "unconnected-(SV5-Pad14)") (class "Default")
      (node (ref "SV5") (pin "14") (pinfunction "14_14") (pintype "passive"))
    )
    (net (code "162") (name "unconnected-(SV7-Pad4)") (class "Default")
      (node (ref "SV7") (pin "4") (pinfunction "4_4") (pintype "passive"))
    )
    (net (code "163") (name "unconnected-(SV7-Pad5)") (class "Default")
      (node (ref "SV7") (pin "5") (pinfunction "5_5") (pintype "passive"))
    )
    (net (code "164") (name "unconnected-(SV7-Pad6)") (class "Default")
      (node (ref "SV7") (pin "6") (pinfunction "6_6") (pintype "passive"))
    )
    (net (code "165") (name "unconnected-(SV7-Pad8)") (class "Default")
      (node (ref "SV7") (pin "8") (pinfunction "8_8") (pintype "passive"))
    )
    (net (code "166") (name "unconnected-(SV7-Pad9)") (class "Default")
      (node (ref "SV7") (pin "9") (pinfunction "9_9") (pintype "passive"))
    )
    (net (code "167") (name "unconnected-(SV7-Pad10)") (class "Default")
      (node (ref "SV7") (pin "10") (pinfunction "10_10") (pintype "passive"))
    )
    (net (code "168") (name "unconnected-(SV7-Pad11)") (class "Default")
      (node (ref "SV7") (pin "11") (pinfunction "11_11") (pintype "passive"))
    )
    (net (code "169") (name "unconnected-(SV8-Pad4)") (class "Default")
      (node (ref "SV8") (pin "4") (pinfunction "4_4") (pintype "passive"))
    )
    (net (code "170") (name "unconnected-(SV8-Pad5)") (class "Default")
      (node (ref "SV8") (pin "5") (pinfunction "5_5") (pintype "passive"))
    )
    (net (code "171") (name "unconnected-(SV8-Pad6)") (class "Default")
      (node (ref "SV8") (pin "6") (pinfunction "6_6") (pintype "passive"))
    )
    (net (code "172") (name "unconnected-(SV8-Pad8)") (class "Default")
      (node (ref "SV8") (pin "8") (pinfunction "8_8") (pintype "passive"))
    )
    (net (code "173") (name "unconnected-(SV8-Pad9)") (class "Default")
      (node (ref "SV8") (pin "9") (pinfunction "9_9") (pintype "passive"))
    )
    (net (code "174") (name "unconnected-(SV8-Pad10)") (class "Default")
      (node (ref "SV8") (pin "10") (pinfunction "10_10") (pintype "passive"))
    )
    (net (code "175") (name "unconnected-(SV8-Pad11)") (class "Default")
      (node (ref "SV8") (pin "11") (pinfunction "11_11") (pintype "passive"))
    )
    (net (code "176") (name "unconnected-(U1-PadAREF)") (class "Default")
      (node (ref "U1") (pin "AREF") (pinfunction "AREF_AREF") (pintype "bidirectional"))
    )
    (net (code "177") (name "unconnected-(U1-PadD0)") (class "Default")
      (node (ref "U1") (pin "D0") (pinfunction "D0_D0") (pintype "bidirectional"))
    )
    (net (code "178") (name "unconnected-(U1-PadD1)") (class "Default")
      (node (ref "U1") (pin "D1") (pinfunction "D1_D1") (pintype "bidirectional"))
    )
    (net (code "179") (name "unconnected-(U1-PadIOREF)") (class "Default")
      (node (ref "U1") (pin "IOREF") (pinfunction "IOREF_IOREF") (pintype "output"))
    )
    (net (code "180") (name "unconnected-(U1-PadRESERVED)") (class "Default")
      (node (ref "U1") (pin "RESERVED") (pinfunction "RESERVED_RESERVED") (pintype "no_connect"))
    )
    (net (code "181") (name "unconnected-(U1-PadSCL)") (class "Default")
      (node (ref "U1") (pin "SCL") (pinfunction "SCL_SCL") (pintype "bidirectional"))
    )
    (net (code "182") (name "unconnected-(U1-PadSDA)") (class "Default")
      (node (ref "U1") (pin "SDA") (pinfunction "SDA_SDA") (pintype "bidirectional"))
    )
    (net (code "183") (name "unconnected-(U1-{slash}RESET-PadRESET)") (class "Default")
      (node (ref "U1") (pin "RESET") (pinfunction "/RESET_RESET") (pintype "bidirectional"))
    )
  )
)
